# Backer_Boards_01April15.net
KiCad netlist of a schematic drawn in EAGLE
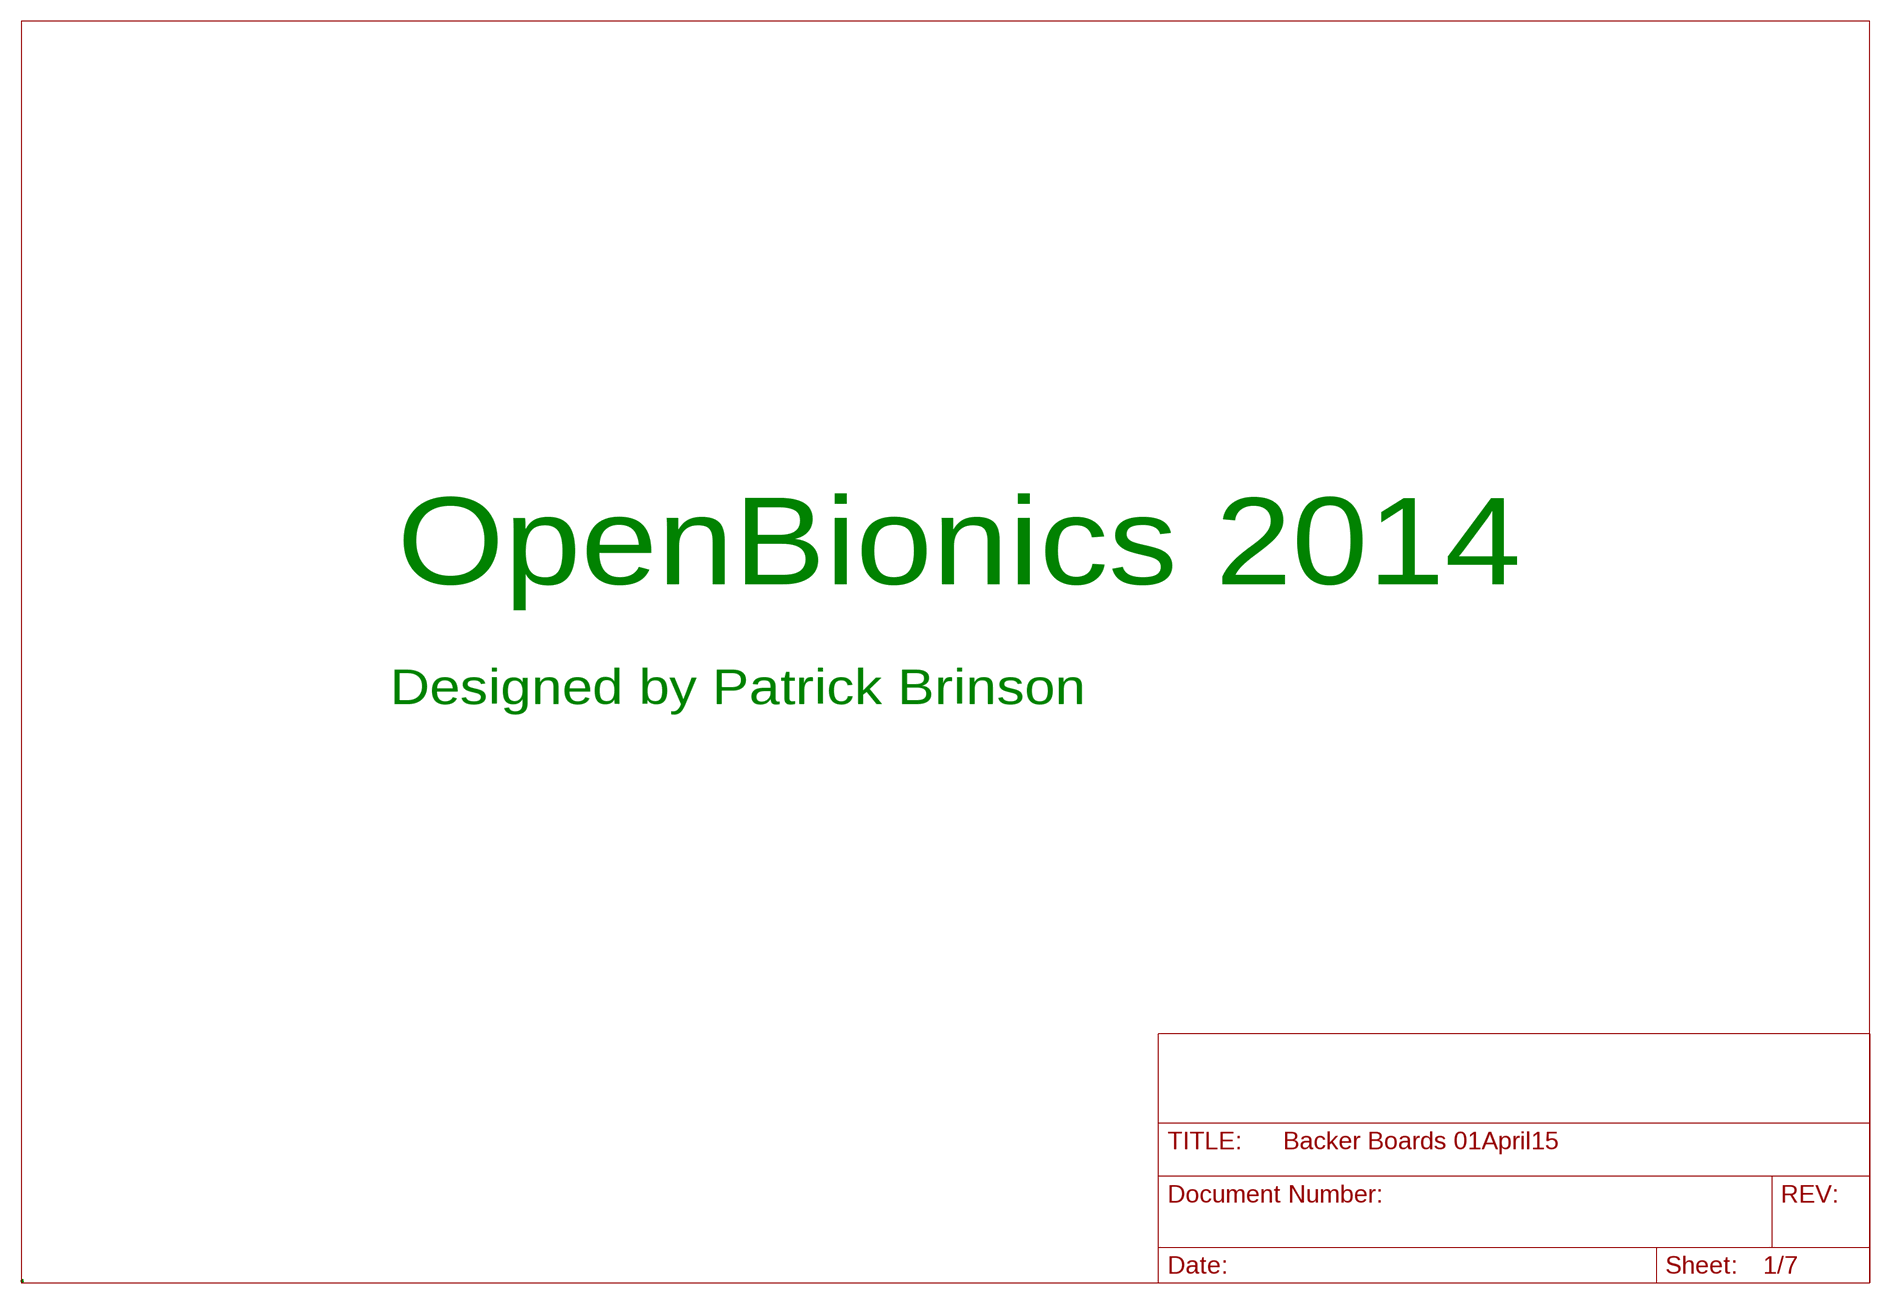
[diagram p0: schematic, sheet 1]
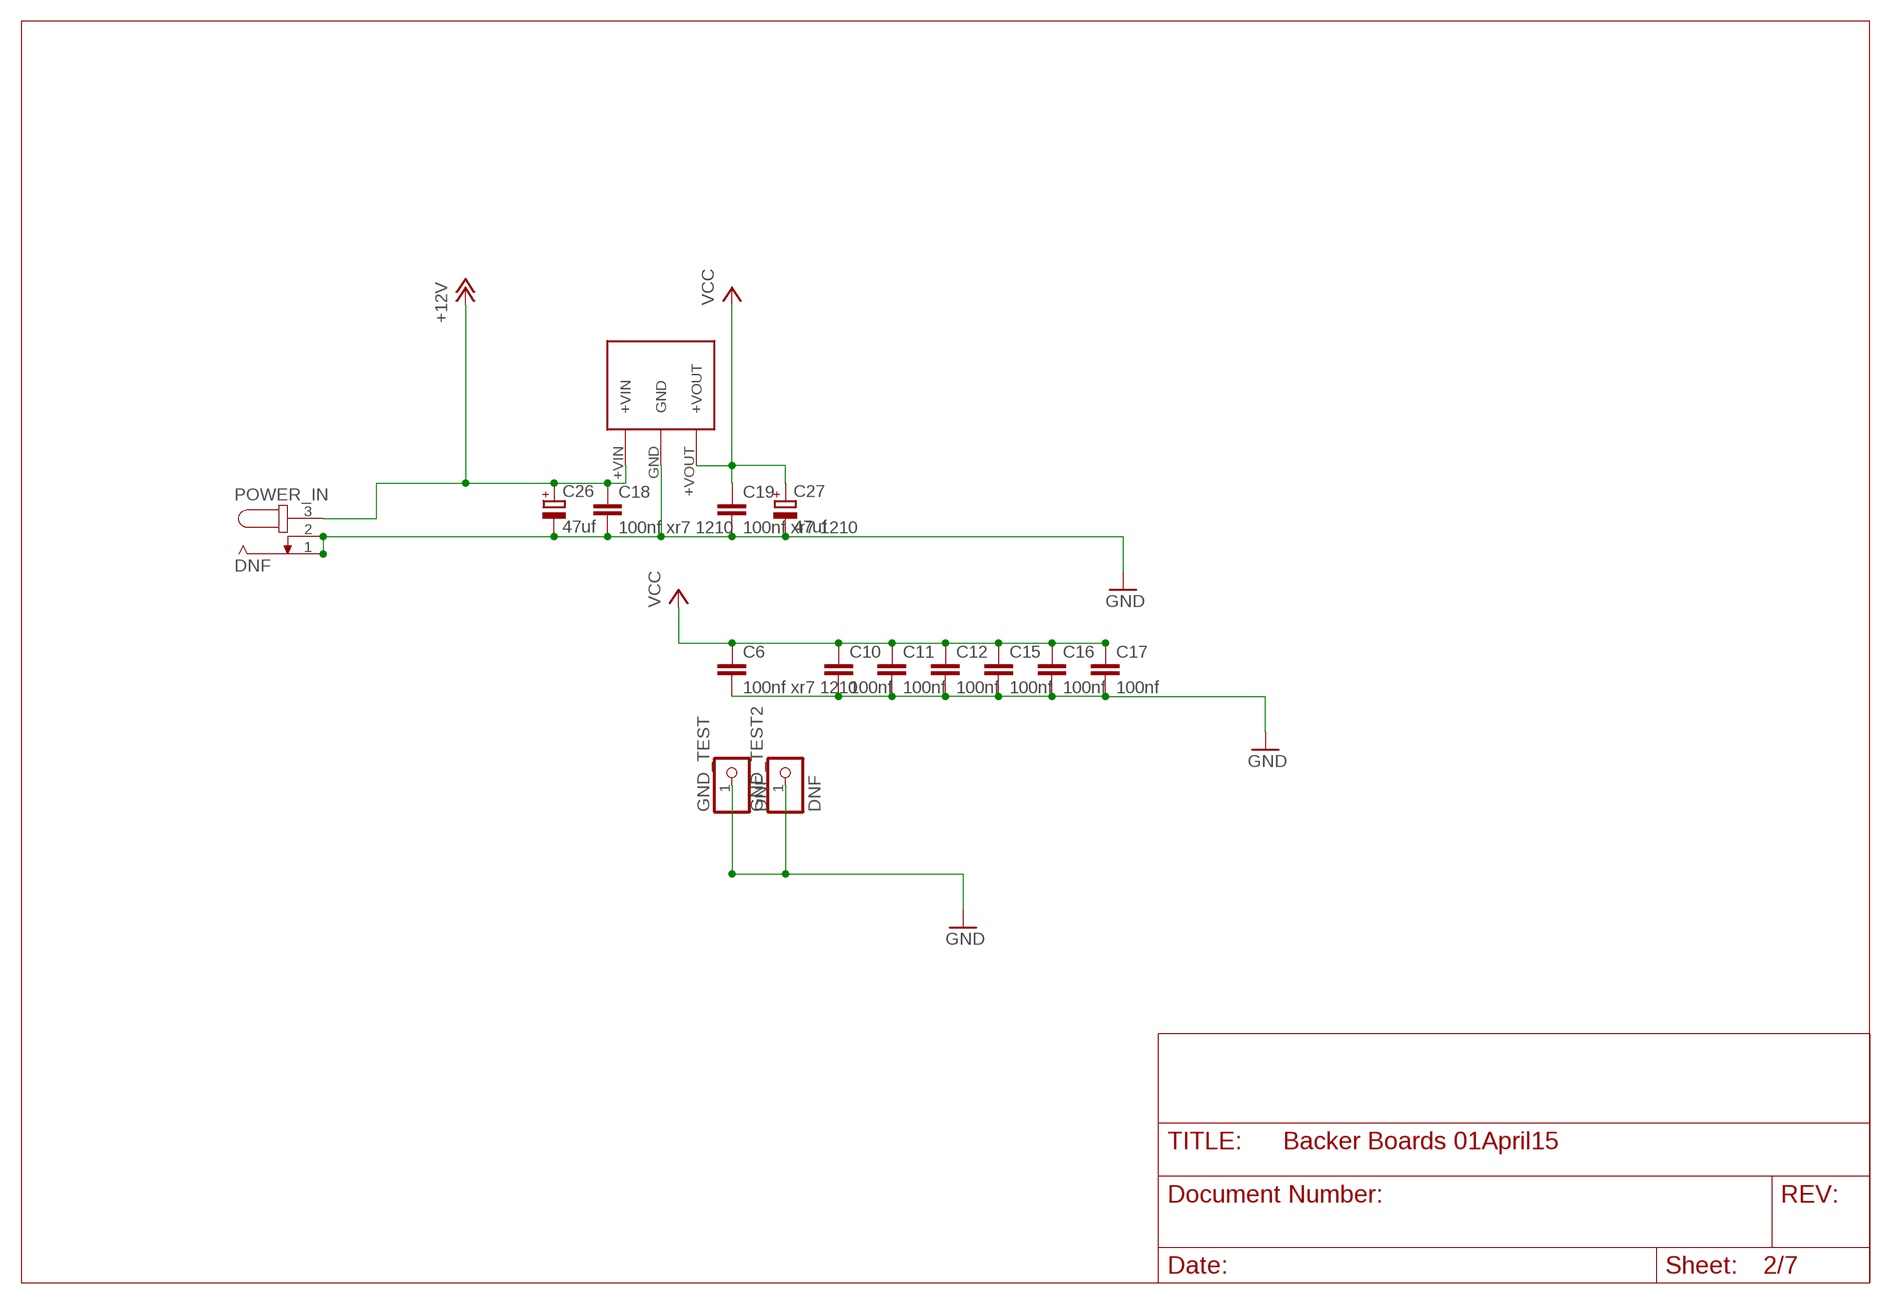
[diagram p1: schematic, sheet 2]
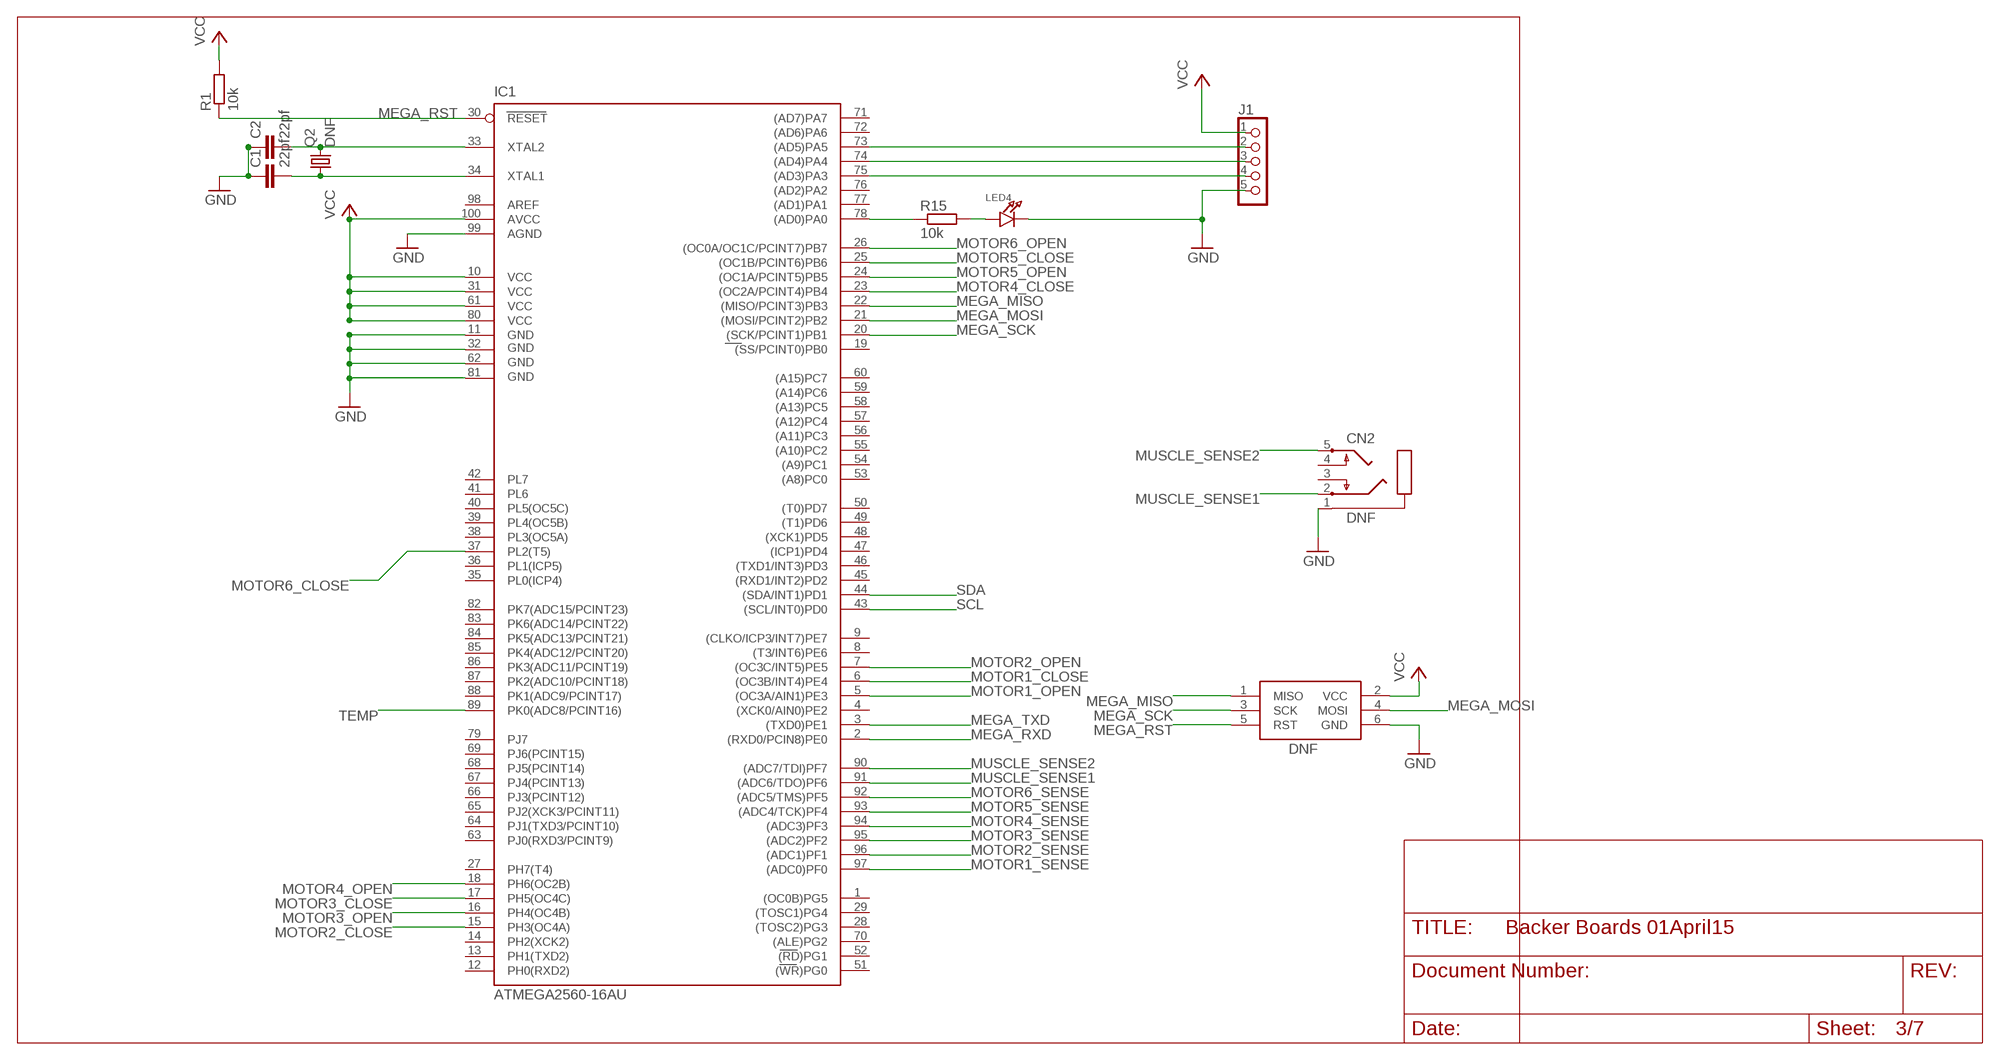
[diagram p2: schematic, sheet 3]
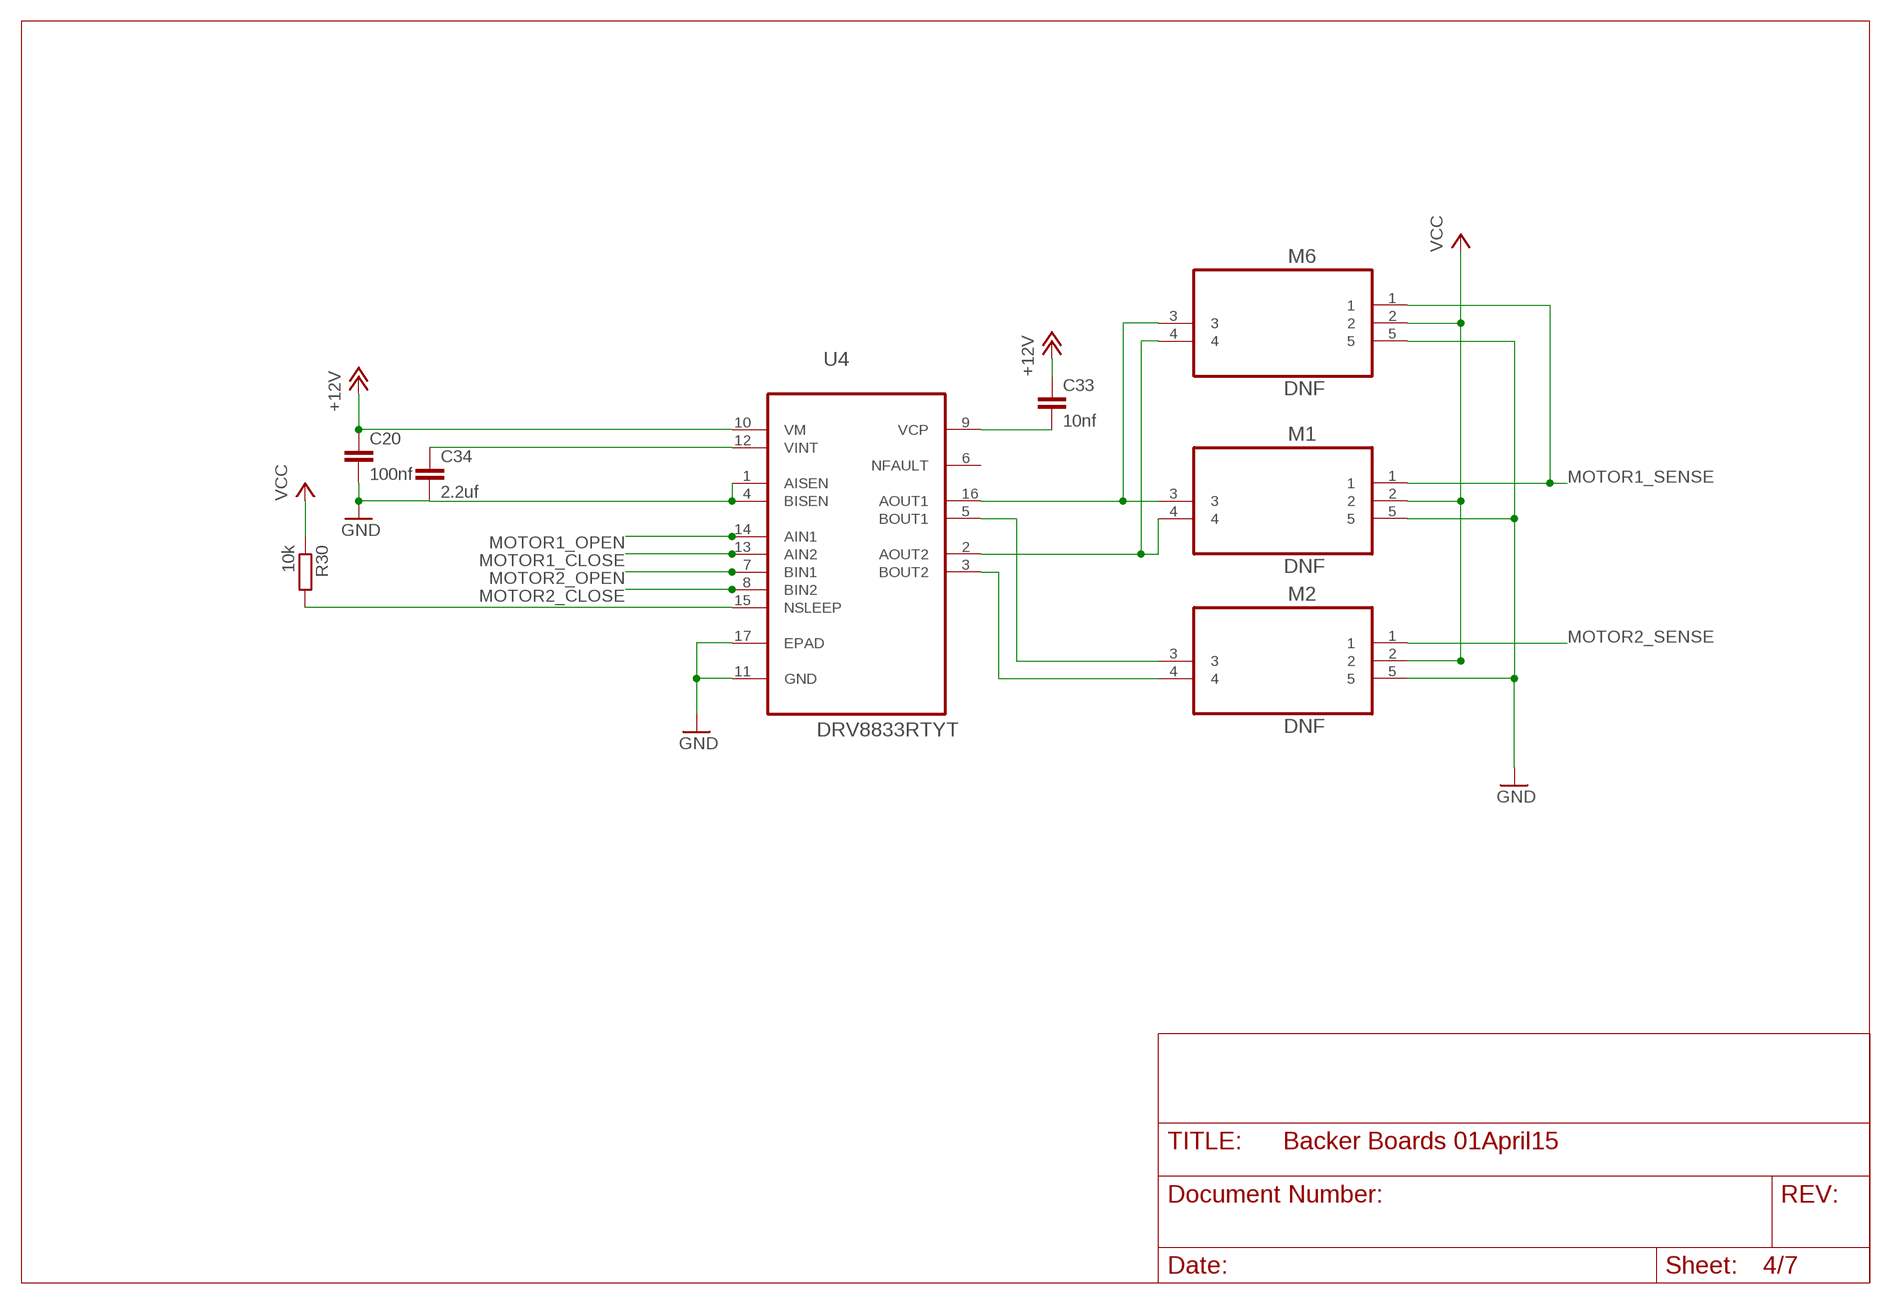
[diagram p3: schematic, sheet 4]
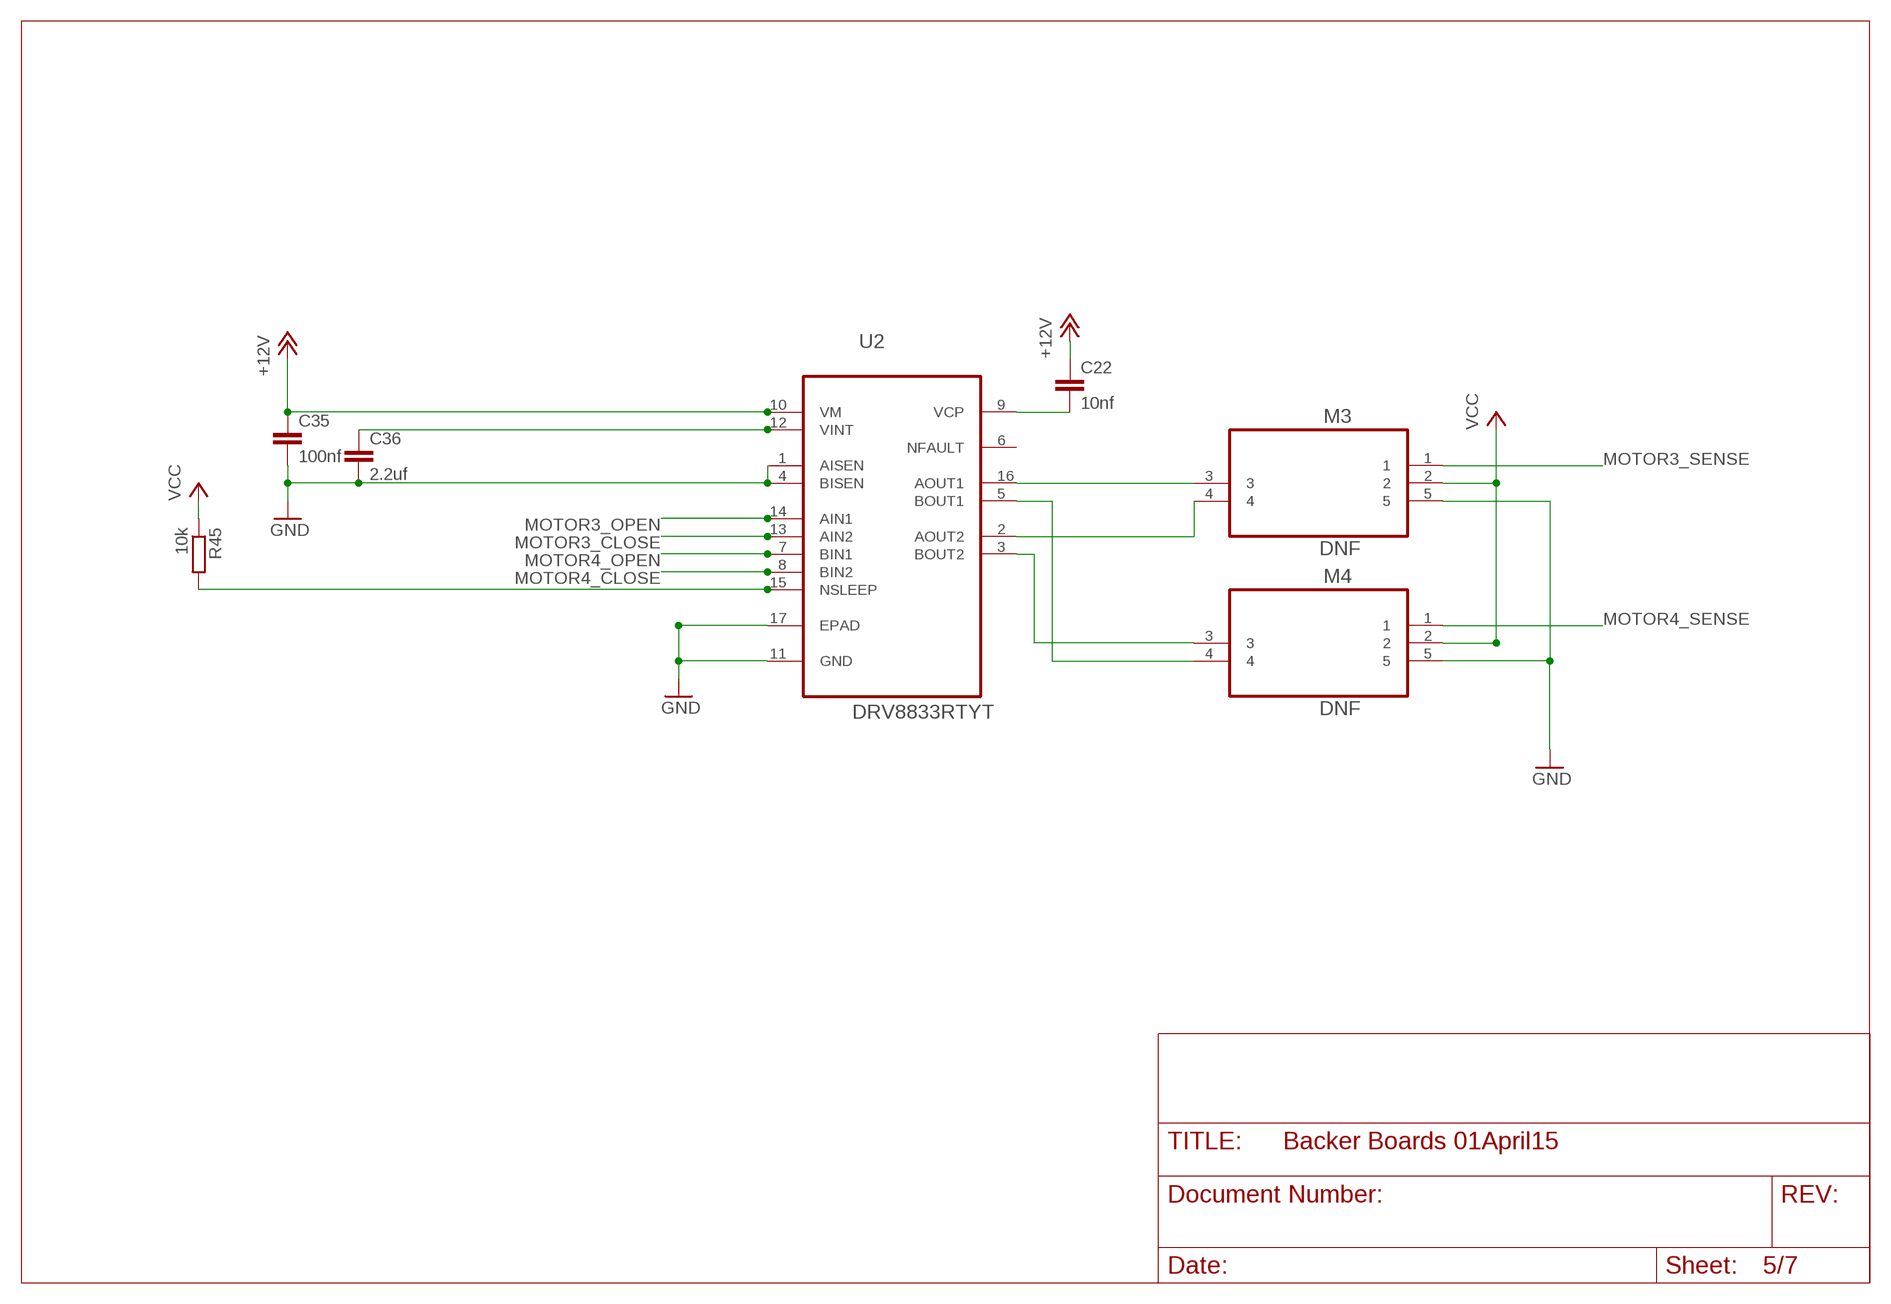
[diagram p4: schematic, sheet 5]
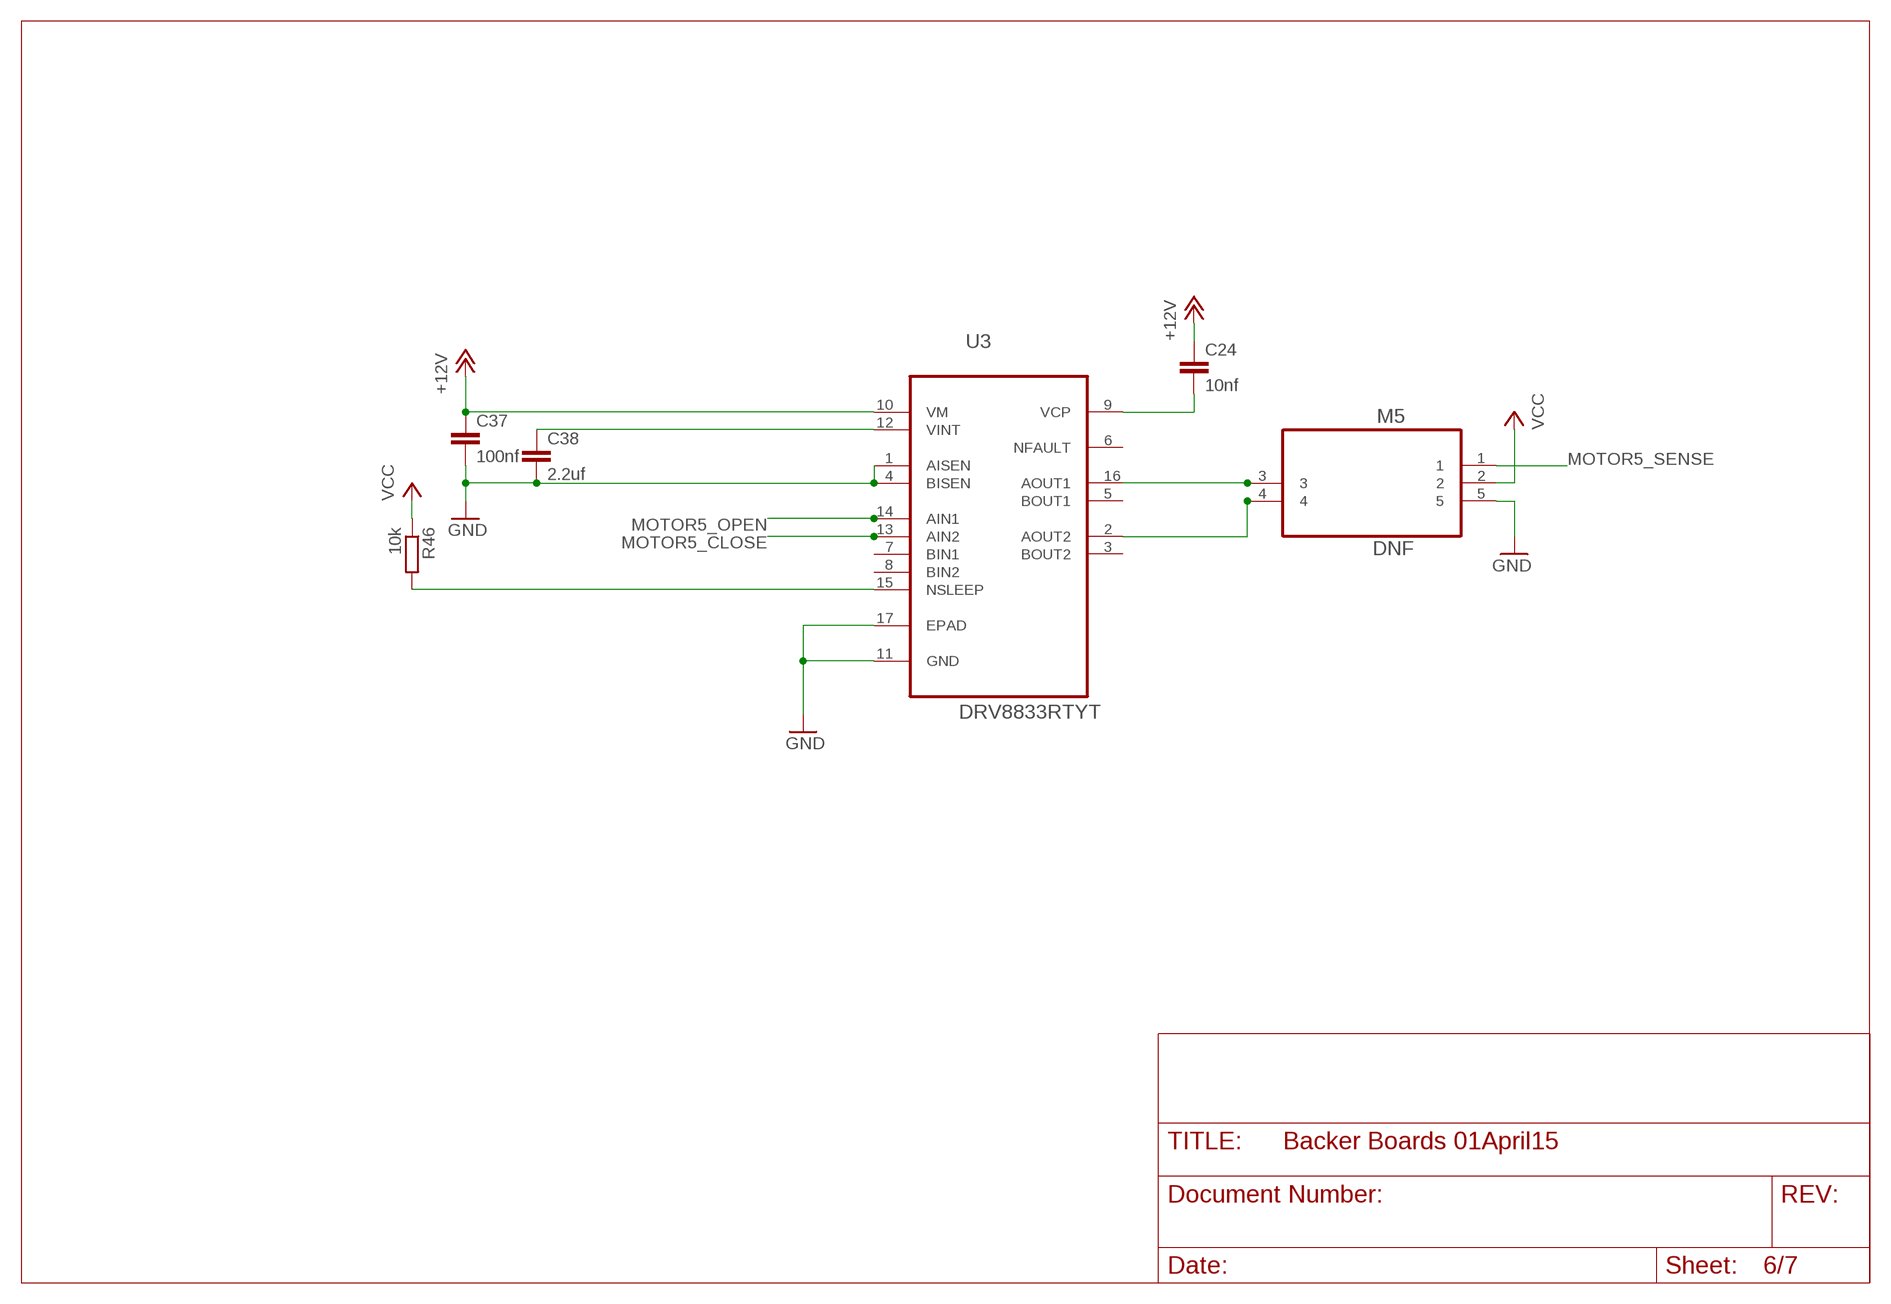
[diagram p5: schematic, sheet 6]
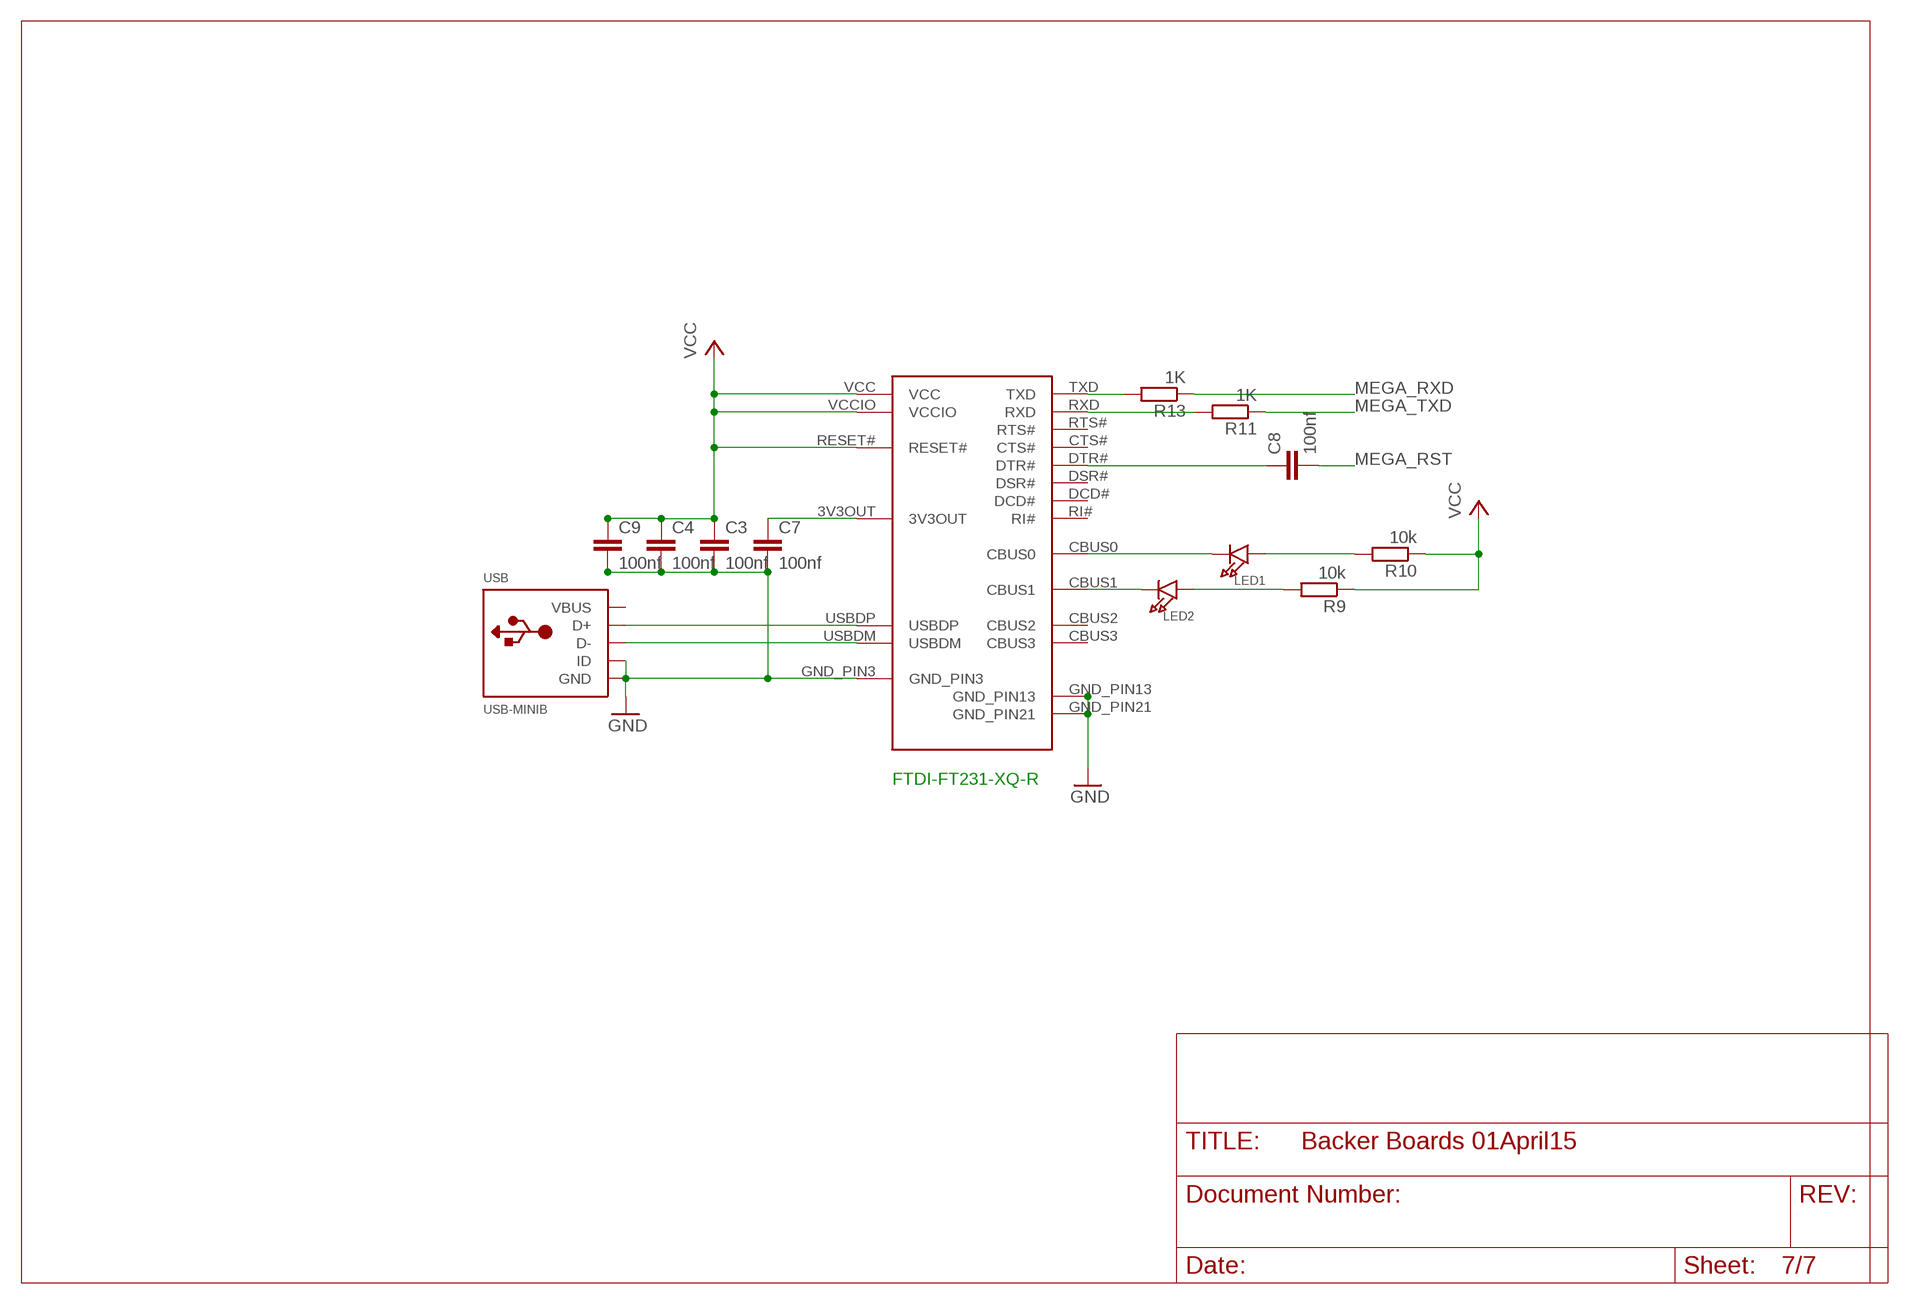
[diagram p6: schematic, sheet 7]

(export (version "E")
  (design (tool "Eeschema 10.0.6"))
  (components
    (comp (ref "C24")
      (value "10nf")
      (footprint "eagle-import:C0603")
      (libsource (lib "eagle-import") (part "C-EUC0603"))
    )
    (comp (ref "C37")
      (value "100nf")
      (footprint "eagle-import:C0603")
      (libsource (lib "eagle-import") (part "C-EUC0603"))
    )
    (comp (ref "C38")
      (value "2.2uf")
      (footprint "eagle-import:C0603")
      (libsource (lib "eagle-import") (part "C-EUC0603"))
    )
    (comp (ref "M5")
      (value "DNF")
      (footprint "eagle-import:FCI_SFW5R-1STE1LF")
      (fields (field (name "MPN") "SFW5R-1STE1LF"))
      (libsource (lib "eagle-import") (part "SFW5R-1STE1LF"))
    )
    (comp (ref "R46")
      (value "10k")
      (footprint "eagle-import:R0603")
      (libsource (lib "eagle-import") (part "R-EU_R0603"))
    )
    (comp (ref "U3")
      (value "DRV8833RTYT")
      (footprint "eagle-import:QFN65P400X400X80-17N")
      (fields (field (name "MPN") "DRV8833RTYT "))
      (libsource (lib "eagle-import") (part "DRV8833RTYT"))
    )
    (comp (ref "C1")
      (value "22pf")
      (footprint "eagle-import:C0603")
      (libsource (lib "eagle-import") (part "C-EUC0603"))
    )
    (comp (ref "C2")
      (value "22pf")
      (footprint "eagle-import:C0603")
      (libsource (lib "eagle-import") (part "C-EUC0603"))
    )
    (comp (ref "CN2")
      (value "DNF")
      (footprint "eagle-import:STX3100")
      (libsource (lib "eagle-import") (part "AUDIO_STEREOJACK"))
    )
    (comp (ref "DNF")
      (value "AVRISP-6")
      (footprint "eagle-import:AVRISP")
      (libsource (lib "eagle-import") (part "AVRISP-6"))
    )
    (comp (ref "IC1")
      (value "ATMEGA2560-16AU")
      (footprint "eagle-import:TQFP100")
      (libsource (lib "eagle-import") (part "ATMEGAAU2560-16"))
    )
    (comp (ref "J1")
      (value "DNF")
      (footprint "eagle-import:M1X5")
      (libsource (lib "eagle-import") (part "CON_HEADER_1X05-PTH"))
    )
    (comp (ref "LED4")
      (value "LED0805")
      (footprint "eagle-import:CHIPLED_0805")
      (libsource (lib "eagle-import") (part "LED0805"))
    )
    (comp (ref "Q2")
      (value "DNF")
      (footprint "eagle-import:HC49_S")
      (libsource (lib "eagle-import") (part "CRYSTALHC49S"))
    )
    (comp (ref "R1")
      (value "10k")
      (footprint "eagle-import:R0603")
      (libsource (lib "eagle-import") (part "R-EU_R0603"))
    )
    (comp (ref "R15")
      (value "10k")
      (footprint "eagle-import:R0603")
      (libsource (lib "eagle-import") (part "R-EU_R0603"))
    )
    (comp (ref "5V_REG")
      (value "DNF")
      (footprint "eagle-import:5V_RECOM_0.5A_REGULATOR")
      (libsource (lib "eagle-import") (part "5V_RECOM_0.5A_REGULATOR"))
    )
    (comp (ref "C6")
      (value "100nf xr7 1210")
      (footprint "eagle-import:C1210")
      (libsource (lib "eagle-import") (part "C-EUC1210"))
    )
    (comp (ref "C10")
      (value "100nf")
      (footprint "eagle-import:C0603")
      (libsource (lib "eagle-import") (part "C-EUC0603"))
    )
    (comp (ref "C11")
      (value "100nf")
      (footprint "eagle-import:C0603")
      (libsource (lib "eagle-import") (part "C-EUC0603"))
    )
    (comp (ref "C12")
      (value "100nf")
      (footprint "eagle-import:C0603")
      (libsource (lib "eagle-import") (part "C-EUC0603"))
    )
    (comp (ref "C15")
      (value "100nf")
      (footprint "eagle-import:C0603")
      (libsource (lib "eagle-import") (part "C-EUC0603"))
    )
    (comp (ref "C16")
      (value "100nf")
      (footprint "eagle-import:C0603")
      (libsource (lib "eagle-import") (part "C-EUC0603"))
    )
    (comp (ref "C17")
      (value "100nf")
      (footprint "eagle-import:C0603")
      (libsource (lib "eagle-import") (part "C-EUC0603"))
    )
    (comp (ref "C18")
      (value "100nf xr7 1210")
      (footprint "eagle-import:C1210")
      (libsource (lib "eagle-import") (part "C-EUC1210"))
    )
    (comp (ref "C19")
      (value "100nf xr7 1210")
      (footprint "eagle-import:C1210")
      (libsource (lib "eagle-import") (part "C-EUC1210"))
    )
    (comp (ref "C26")
      (value "47uf")
      (footprint "eagle-import:PANASONIC_C")
      (libsource (lib "eagle-import") (part "CPOL-EUC"))
    )
    (comp (ref "C27")
      (value "47uf")
      (footprint "eagle-import:PANASONIC_C")
      (libsource (lib "eagle-import") (part "CPOL-EUC"))
    )
    (comp (ref "GND_TEST")
      (value "DNF")
      (footprint "eagle-import:1X01_ROUND")
      (libsource (lib "eagle-import") (part "HEADER-1X1ROUND"))
    )
    (comp (ref "GND_TEST2")
      (value "DNF")
      (footprint "eagle-import:1X01_ROUND")
      (libsource (lib "eagle-import") (part "HEADER-1X1ROUND"))
    )
    (comp (ref "POWER_IN")
      (value "DNF")
      (footprint "eagle-import:SPC4078")
      (libsource (lib "eagle-import") (part "JACK-PLUG1"))
    )
    (comp (ref "C20")
      (value "100nf")
      (footprint "eagle-import:C0603")
      (libsource (lib "eagle-import") (part "C-EUC0603"))
    )
    (comp (ref "C33")
      (value "10nf")
      (footprint "eagle-import:C0603")
      (libsource (lib "eagle-import") (part "C-EUC0603"))
    )
    (comp (ref "C34")
      (value "2.2uf")
      (footprint "eagle-import:C0603")
      (libsource (lib "eagle-import") (part "C-EUC0603"))
    )
    (comp (ref "M1")
      (value "DNF")
      (footprint "eagle-import:FCI_SFW5R-1STE1LF")
      (fields (field (name "MPN") "SFW5R-1STE1LF"))
      (libsource (lib "eagle-import") (part "SFW5R-1STE1LF"))
    )
    (comp (ref "M2")
      (value "DNF")
      (footprint "eagle-import:FCI_SFW5R-1STE1LF")
      (fields (field (name "MPN") "SFW5R-1STE1LF"))
      (libsource (lib "eagle-import") (part "SFW5R-1STE1LF"))
    )
    (comp (ref "M6")
      (value "DNF")
      (footprint "eagle-import:FCI_SFW5R-1STE1LF")
      (fields (field (name "MPN") "SFW5R-1STE1LF"))
      (libsource (lib "eagle-import") (part "SFW5R-1STE1LF"))
    )
    (comp (ref "R30")
      (value "10k")
      (footprint "eagle-import:R0603")
      (libsource (lib "eagle-import") (part "R-EU_R0603"))
    )
    (comp (ref "U4")
      (value "DRV8833RTYT")
      (footprint "eagle-import:QFN65P400X400X80-17N")
      (fields (field (name "MPN") "DRV8833RTYT "))
      (libsource (lib "eagle-import") (part "DRV8833RTYT"))
    )
    (comp (ref "C3")
      (value "100nf")
      (footprint "eagle-import:C0603")
      (libsource (lib "eagle-import") (part "C-EUC0603"))
    )
    (comp (ref "C4")
      (value "100nf")
      (footprint "eagle-import:C0603")
      (libsource (lib "eagle-import") (part "C-EUC0603"))
    )
    (comp (ref "C7")
      (value "100nf")
      (footprint "eagle-import:C0603")
      (libsource (lib "eagle-import") (part "C-EUC0603"))
    )
    (comp (ref "C8")
      (value "100nf")
      (footprint "eagle-import:C0603")
      (libsource (lib "eagle-import") (part "C-EUC0603"))
    )
    (comp (ref "C9")
      (value "100nf")
      (footprint "eagle-import:C0603")
      (libsource (lib "eagle-import") (part "C-EUC0603"))
    )
    (comp (ref "FTDI-FT231-XQ-R")
      (value "FT231XQ-R")
      (footprint "eagle-import:FTDI_FT231XQ-R_PACKAGE")
      (libsource (lib "eagle-import") (part "FT231XQ-R"))
    )
    (comp (ref "LED1")
      (value "LED0805")
      (footprint "eagle-import:CHIPLED_0805")
      (libsource (lib "eagle-import") (part "LED0805"))
    )
    (comp (ref "LED2")
      (value "LED0805")
      (footprint "eagle-import:CHIPLED_0805")
      (libsource (lib "eagle-import") (part "LED0805"))
    )
    (comp (ref "R9")
      (value "10k")
      (footprint "eagle-import:R0603")
      (libsource (lib "eagle-import") (part "R-EU_R0603"))
    )
    (comp (ref "R10")
      (value "10k")
      (footprint "eagle-import:R0603")
      (libsource (lib "eagle-import") (part "R-EU_R0603"))
    )
    (comp (ref "R11")
      (value "1K")
      (footprint "eagle-import:R0603")
      (libsource (lib "eagle-import") (part "R-EU_R0603"))
    )
    (comp (ref "R13")
      (value "1K")
      (footprint "eagle-import:R0603")
      (libsource (lib "eagle-import") (part "R-EU_R0603"))
    )
    (comp (ref "USB")
      (value "USB-MINIB")
      (footprint "eagle-import:USB-MINIB")
      (libsource (lib "eagle-import") (part "USBMINIB"))
    )
    (comp (ref "C22")
      (value "10nf")
      (footprint "eagle-import:C0603")
      (libsource (lib "eagle-import") (part "C-EUC0603"))
    )
    (comp (ref "C35")
      (value "100nf")
      (footprint "eagle-import:C0603")
      (libsource (lib "eagle-import") (part "C-EUC0603"))
    )
    (comp (ref "C36")
      (value "2.2uf")
      (footprint "eagle-import:C0603")
      (libsource (lib "eagle-import") (part "C-EUC0603"))
    )
    (comp (ref "M3")
      (value "DNF")
      (footprint "eagle-import:FCI_SFW5R-1STE1LF")
      (fields (field (name "MPN") "SFW5R-1STE1LF"))
      (libsource (lib "eagle-import") (part "SFW5R-1STE1LF"))
    )
    (comp (ref "M4")
      (value "DNF")
      (footprint "eagle-import:FCI_SFW5R-1STE1LF")
      (fields (field (name "MPN") "SFW5R-1STE1LF"))
      (libsource (lib "eagle-import") (part "SFW5R-1STE1LF"))
    )
    (comp (ref "R45")
      (value "10k")
      (footprint "eagle-import:R0603")
      (libsource (lib "eagle-import") (part "R-EU_R0603"))
    )
    (comp (ref "U2")
      (value "DRV8833RTYT")
      (footprint "eagle-import:QFN65P400X400X80-17N")
      (fields (field (name "MPN") "DRV8833RTYT "))
      (libsource (lib "eagle-import") (part "DRV8833RTYT"))
    )
  )
  (nets
    (net (code "1") (name "+12V") (class "Default")
      (node (ref "5V_REG") (pin "+VIN") (pinfunction "+VIN_+VIN") (pintype "bidirectional"))
      (node (ref "C18") (pin "1") (pinfunction "1_1") (pintype "passive"))
      (node (ref "C20") (pin "1") (pinfunction "1_1") (pintype "passive"))
      (node (ref "C22") (pin "1") (pinfunction "1_1") (pintype "passive"))
      (node (ref "C24") (pin "1") (pinfunction "1_1") (pintype "passive"))
      (node (ref "C26") (pin "+") (pinfunction "+_+") (pintype "passive"))
      (node (ref "C33") (pin "1") (pinfunction "1_1") (pintype "passive"))
      (node (ref "C35") (pin "1") (pinfunction "1_1") (pintype "passive"))
      (node (ref "C37") (pin "1") (pinfunction "1_1") (pintype "passive"))
      (node (ref "POWER_IN") (pin "3") (pinfunction "3_3") (pintype "passive"))
      (node (ref "U2") (pin "10") (pinfunction "VM_10") (pintype "power_in"))
      (node (ref "U3") (pin "10") (pinfunction "VM_10") (pintype "power_in"))
      (node (ref "U4") (pin "10") (pinfunction "VM_10") (pintype "power_in"))
    )
    (net (code "2") (name "GND") (class "Default")
      (node (ref "5V_REG") (pin "GND") (pinfunction "GND_GND") (pintype "bidirectional"))
      (node (ref "C1") (pin "1") (pinfunction "1_1") (pintype "passive"))
      (node (ref "C10") (pin "2") (pinfunction "2_2") (pintype "passive"))
      (node (ref "C11") (pin "2") (pinfunction "2_2") (pintype "passive"))
      (node (ref "C12") (pin "2") (pinfunction "2_2") (pintype "passive"))
      (node (ref "C15") (pin "2") (pinfunction "2_2") (pintype "passive"))
      (node (ref "C16") (pin "2") (pinfunction "2_2") (pintype "passive"))
      (node (ref "C17") (pin "2") (pinfunction "2_2") (pintype "passive"))
      (node (ref "C18") (pin "2") (pinfunction "2_2") (pintype "passive"))
      (node (ref "C19") (pin "2") (pinfunction "2_2") (pintype "passive"))
      (node (ref "C2") (pin "1") (pinfunction "1_1") (pintype "passive"))
      (node (ref "C20") (pin "2") (pinfunction "2_2") (pintype "passive"))
      (node (ref "C26") (pin "-") (pinfunction "-_-") (pintype "passive"))
      (node (ref "C27") (pin "-") (pinfunction "-_-") (pintype "passive"))
      (node (ref "C3") (pin "2") (pinfunction "2_2") (pintype "passive"))
      (node (ref "C34") (pin "2") (pinfunction "2_2") (pintype "passive"))
      (node (ref "C35") (pin "2") (pinfunction "2_2") (pintype "passive"))
      (node (ref "C36") (pin "2") (pinfunction "2_2") (pintype "passive"))
      (node (ref "C37") (pin "2") (pinfunction "2_2") (pintype "passive"))
      (node (ref "C38") (pin "2") (pinfunction "2_2") (pintype "passive"))
      (node (ref "C4") (pin "2") (pinfunction "2_2") (pintype "passive"))
      (node (ref "C6") (pin "2") (pinfunction "2_2") (pintype "passive"))
      (node (ref "C7") (pin "2") (pinfunction "2_2") (pintype "passive"))
      (node (ref "C9") (pin "2") (pinfunction "2_2") (pintype "passive"))
      (node (ref "CN2") (pin "1") (pinfunction "1_1") (pintype "passive"))
      (node (ref "DNF") (pin "6") (pinfunction "GND_6") (pintype "power_in"))
      (node (ref "FTDI-FT231-XQ-R") (pin "GND_PIN13") (pinfunction "GND_PIN13_GND_PIN13") (pintype "bidirectional"))
      (node (ref "FTDI-FT231-XQ-R") (pin "GND_PIN21") (pinfunction "GND_PIN21_GND_PIN21") (pintype "bidirectional"))
      (node (ref "FTDI-FT231-XQ-R") (pin "GND_PIN3") (pinfunction "GND_PIN3_GND_PIN3") (pintype "bidirectional"))
      (node (ref "GND_TEST") (pin "1") (pinfunction "1_1") (pintype "passive"))
      (node (ref "GND_TEST2") (pin "1") (pinfunction "1_1") (pintype "passive"))
      (node (ref "IC1") (pin "11") (pinfunction "GND_11") (pintype "power_in"))
      (node (ref "IC1") (pin "32") (pinfunction "GND1_32") (pintype "power_in"))
      (node (ref "IC1") (pin "62") (pinfunction "GND2_62") (pintype "power_in"))
      (node (ref "IC1") (pin "81") (pinfunction "GND3_81") (pintype "power_in"))
      (node (ref "IC1") (pin "99") (pinfunction "AGND_99") (pintype "power_in"))
      (node (ref "J1") (pin "5") (pinfunction "5_5") (pintype "bidirectional"))
      (node (ref "LED4") (pin "C") (pinfunction "C_C") (pintype "passive"))
      (node (ref "M1") (pin "5") (pinfunction "5_5") (pintype "passive"))
      (node (ref "M2") (pin "5") (pinfunction "5_5") (pintype "passive"))
      (node (ref "M3") (pin "5") (pinfunction "5_5") (pintype "passive"))
      (node (ref "M4") (pin "5") (pinfunction "5_5") (pintype "passive"))
      (node (ref "M5") (pin "5") (pinfunction "5_5") (pintype "passive"))
      (node (ref "M6") (pin "5") (pinfunction "5_5") (pintype "passive"))
      (node (ref "POWER_IN") (pin "1") (pinfunction "1_1") (pintype "passive"))
      (node (ref "POWER_IN") (pin "2") (pinfunction "2_2") (pintype "passive"))
      (node (ref "U2") (pin "1") (pinfunction "AISEN_1") (pintype "bidirectional"))
      (node (ref "U2") (pin "11") (pinfunction "GND_11") (pintype "passive"))
      (node (ref "U2") (pin "17") (pinfunction "EPAD_17") (pintype "passive"))
      (node (ref "U2") (pin "4") (pinfunction "BISEN_4") (pintype "bidirectional"))
      (node (ref "U3") (pin "1") (pinfunction "AISEN_1") (pintype "bidirectional"))
      (node (ref "U3") (pin "11") (pinfunction "GND_11") (pintype "passive"))
      (node (ref "U3") (pin "17") (pinfunction "EPAD_17") (pintype "passive"))
      (node (ref "U3") (pin "4") (pinfunction "BISEN_4") (pintype "bidirectional"))
      (node (ref "U4") (pin "1") (pinfunction "AISEN_1") (pintype "bidirectional"))
      (node (ref "U4") (pin "11") (pinfunction "GND_11") (pintype "passive"))
      (node (ref "U4") (pin "17") (pinfunction "EPAD_17") (pintype "passive"))
      (node (ref "U4") (pin "4") (pinfunction "BISEN_4") (pintype "bidirectional"))
      (node (ref "USB") (pin "GND") (pinfunction "GND_GND") (pintype "power_in"))
      (node (ref "USB") (pin "ID") (pinfunction "ID_ID") (pintype "bidirectional"))
    )
    (net (code "3") (name "MEGA_MISO") (class "Default")
      (node (ref "DNF") (pin "1") (pinfunction "MISO_1") (pintype "input"))
      (node (ref "IC1") (pin "22") (pinfunction "(MISO/PCINT3)PB3_22") (pintype "bidirectional"))
    )
    (net (code "4") (name "MEGA_MOSI") (class "Default")
      (node (ref "DNF") (pin "4") (pinfunction "MOSI_4") (pintype "output"))
      (node (ref "IC1") (pin "21") (pinfunction "(MOSI/PCINT2)PB2_21") (pintype "bidirectional"))
    )
    (net (code "5") (name "MEGA_RST") (class "Default")
      (node (ref "C8") (pin "2") (pinfunction "2_2") (pintype "passive"))
      (node (ref "DNF") (pin "5") (pinfunction "RST_5") (pintype "output"))
      (node (ref "IC1") (pin "30") (pinfunction "RESET_30") (pintype "input"))
      (node (ref "R1") (pin "1") (pinfunction "1_1") (pintype "passive"))
    )
    (net (code "6") (name "MEGA_RXD") (class "Default")
      (node (ref "IC1") (pin "2") (pinfunction "(RXD0/PCIN8)PE0_2") (pintype "bidirectional"))
      (node (ref "R13") (pin "1") (pinfunction "1_1") (pintype "passive"))
    )
    (net (code "7") (name "MEGA_SCK") (class "Default")
      (node (ref "DNF") (pin "3") (pinfunction "SCK_3") (pintype "output"))
      (node (ref "IC1") (pin "20") (pinfunction "(SCK/PCINT1)PB1_20") (pintype "bidirectional"))
    )
    (net (code "8") (name "MEGA_TXD") (class "Default")
      (node (ref "IC1") (pin "3") (pinfunction "(TXD0)PE1_3") (pintype "bidirectional"))
      (node (ref "R11") (pin "1") (pinfunction "1_1") (pintype "passive"))
    )
    (net (code "9") (name "MOTOR1_CLOSE") (class "Default")
      (node (ref "IC1") (pin "6") (pinfunction "(OC3B/INT4)PE4_6") (pintype "bidirectional"))
      (node (ref "U4") (pin "13") (pinfunction "AIN2_13") (pintype "input"))
    )
    (net (code "10") (name "MOTOR1_OPEN") (class "Default")
      (node (ref "IC1") (pin "5") (pinfunction "(OC3A/AIN1)PE3_5") (pintype "bidirectional"))
      (node (ref "U4") (pin "14") (pinfunction "AIN1_14") (pintype "input"))
    )
    (net (code "11") (name "MOTOR1_SENSE") (class "Default")
      (node (ref "IC1") (pin "97") (pinfunction "(ADC0)PF0_97") (pintype "bidirectional"))
      (node (ref "M1") (pin "1") (pinfunction "1_1") (pintype "passive"))
      (node (ref "M6") (pin "1") (pinfunction "1_1") (pintype "passive"))
    )
    (net (code "12") (name "MOTOR2_CLOSE") (class "Default")
      (node (ref "IC1") (pin "15") (pinfunction "PH3(OC4A)_15") (pintype "bidirectional"))
      (node (ref "U4") (pin "8") (pinfunction "BIN2_8") (pintype "input"))
    )
    (net (code "13") (name "MOTOR2_OPEN") (class "Default")
      (node (ref "IC1") (pin "7") (pinfunction "(OC3C/INT5)PE5_7") (pintype "bidirectional"))
      (node (ref "U4") (pin "7") (pinfunction "BIN1_7") (pintype "input"))
    )
    (net (code "14") (name "MOTOR2_SENSE") (class "Default")
      (node (ref "IC1") (pin "96") (pinfunction "(ADC1)PF1_96") (pintype "bidirectional"))
      (node (ref "M2") (pin "1") (pinfunction "1_1") (pintype "passive"))
    )
    (net (code "15") (name "MOTOR3_CLOSE") (class "Default")
      (node (ref "IC1") (pin "17") (pinfunction "PH5(OC4C)_17") (pintype "bidirectional"))
      (node (ref "U2") (pin "13") (pinfunction "AIN2_13") (pintype "input"))
    )
    (net (code "16") (name "MOTOR3_OPEN") (class "Default")
      (node (ref "IC1") (pin "16") (pinfunction "PH4(OC4B)_16") (pintype "bidirectional"))
      (node (ref "U2") (pin "14") (pinfunction "AIN1_14") (pintype "input"))
    )
    (net (code "17") (name "MOTOR3_SENSE") (class "Default")
      (node (ref "IC1") (pin "95") (pinfunction "(ADC2)PF2_95") (pintype "bidirectional"))
      (node (ref "M3") (pin "1") (pinfunction "1_1") (pintype "passive"))
    )
    (net (code "18") (name "MOTOR4_CLOSE") (class "Default")
      (node (ref "IC1") (pin "23") (pinfunction "(OC2A/PCINT4)PB4_23") (pintype "bidirectional"))
      (node (ref "U2") (pin "8") (pinfunction "BIN2_8") (pintype "input"))
    )
    (net (code "19") (name "MOTOR4_OPEN") (class "Default")
      (node (ref "IC1") (pin "18") (pinfunction "PH6(OC2B)_18") (pintype "bidirectional"))
      (node (ref "U2") (pin "7") (pinfunction "BIN1_7") (pintype "input"))
    )
    (net (code "20") (name "MOTOR4_SENSE") (class "Default")
      (node (ref "IC1") (pin "94") (pinfunction "(ADC3)PF3_94") (pintype "bidirectional"))
      (node (ref "M4") (pin "1") (pinfunction "1_1") (pintype "passive"))
    )
    (net (code "21") (name "MOTOR5_CLOSE") (class "Default")
      (node (ref "IC1") (pin "25") (pinfunction "(OC1B/PCINT6)PB6_25") (pintype "bidirectional"))
      (node (ref "U3") (pin "13") (pinfunction "AIN2_13") (pintype "input"))
    )
    (net (code "22") (name "MOTOR5_OPEN") (class "Default")
      (node (ref "IC1") (pin "24") (pinfunction "(OC1A/PCINT5)PB5_24") (pintype "bidirectional"))
      (node (ref "U3") (pin "14") (pinfunction "AIN1_14") (pintype "input"))
    )
    (net (code "23") (name "MOTOR5_SENSE") (class "Default")
      (node (ref "IC1") (pin "93") (pinfunction "(ADC4/TCK)PF4_93") (pintype "bidirectional"))
      (node (ref "M5") (pin "1") (pinfunction "1_1") (pintype "passive"))
    )
    (net (code "24") (name "MOTOR6_CLOSE") (class "Default")
      (node (ref "IC1") (pin "37") (pinfunction "PL2(T5)_37") (pintype "bidirectional"))
    )
    (net (code "25") (name "MOTOR6_OPEN") (class "Default")
      (node (ref "IC1") (pin "26") (pinfunction "(OC0A/OC1C/PCINT7)PB7_26") (pintype "bidirectional"))
    )
    (net (code "26") (name "MOTOR6_SENSE") (class "Default")
      (node (ref "IC1") (pin "92") (pinfunction "(ADC5/TMS)PF5_92") (pintype "bidirectional"))
    )
    (net (code "27") (name "MUSCLE_SENSE1") (class "Default")
      (node (ref "CN2") (pin "2") (pinfunction "2_2") (pintype "passive"))
      (node (ref "IC1") (pin "91") (pinfunction "(ADC6/TDO)PF6_91") (pintype "bidirectional"))
    )
    (net (code "28") (name "MUSCLE_SENSE2") (class "Default")
      (node (ref "CN2") (pin "5") (pinfunction "5_5") (pintype "passive"))
      (node (ref "IC1") (pin "90") (pinfunction "(ADC7/TDI)PF7_90") (pintype "bidirectional"))
    )
    (net (code "29") (name "Net-(C7-Pad1)") (class "Default")
      (node (ref "C7") (pin "1") (pinfunction "1_1") (pintype "passive"))
      (node (ref "FTDI-FT231-XQ-R") (pin "3V3OUT") (pinfunction "3V3OUT_3V3OUT") (pintype "bidirectional"))
    )
    (net (code "30") (name "Net-(C8-Pad1)") (class "Default")
      (node (ref "C8") (pin "1") (pinfunction "1_1") (pintype "passive"))
      (node (ref "FTDI-FT231-XQ-R") (pin "DTR#") (pinfunction "DTR#_DTR#") (pintype "bidirectional"))
    )
    (net (code "31") (name "Net-(FTDI-FT231-XQ-R-PadCBUS0)") (class "Default")
      (node (ref "FTDI-FT231-XQ-R") (pin "CBUS0") (pinfunction "CBUS0_CBUS0") (pintype "bidirectional"))
      (node (ref "LED1") (pin "C") (pinfunction "C_C") (pintype "passive"))
    )
    (net (code "32") (name "Net-(FTDI-FT231-XQ-R-PadCBUS1)") (class "Default")
      (node (ref "FTDI-FT231-XQ-R") (pin "CBUS1") (pinfunction "CBUS1_CBUS1") (pintype "bidirectional"))
      (node (ref "LED2") (pin "C") (pinfunction "C_C") (pintype "passive"))
    )
    (net (code "33") (name "Net-(FTDI-FT231-XQ-R-PadRXD)") (class "Default")
      (node (ref "FTDI-FT231-XQ-R") (pin "RXD") (pinfunction "RXD_RXD") (pintype "bidirectional"))
      (node (ref "R11") (pin "2") (pinfunction "2_2") (pintype "passive"))
    )
    (net (code "34") (name "Net-(FTDI-FT231-XQ-R-PadTXD)") (class "Default")
      (node (ref "FTDI-FT231-XQ-R") (pin "TXD") (pinfunction "TXD_TXD") (pintype "bidirectional"))
      (node (ref "R13") (pin "2") (pinfunction "2_2") (pintype "passive"))
    )
    (net (code "35") (name "Net-(FTDI-FT231-XQ-R-PadUSBDM)") (class "Default")
      (node (ref "FTDI-FT231-XQ-R") (pin "USBDM") (pinfunction "USBDM_USBDM") (pintype "bidirectional"))
      (node (ref "USB") (pin "D-") (pinfunction "D-_D-") (pintype "bidirectional"))
    )
    (net (code "36") (name "Net-(FTDI-FT231-XQ-R-PadUSBDP)") (class "Default")
      (node (ref "FTDI-FT231-XQ-R") (pin "USBDP") (pinfunction "USBDP_USBDP") (pintype "bidirectional"))
      (node (ref "USB") (pin "D+") (pinfunction "D+_D+") (pintype "bidirectional"))
    )
    (net (code "37") (name "Net-(IC1-(AD0)PA0)") (class "Default")
      (node (ref "IC1") (pin "78") (pinfunction "(AD0)PA0_78") (pintype "bidirectional"))
      (node (ref "R15") (pin "1") (pinfunction "1_1") (pintype "passive"))
    )
    (net (code "38") (name "Net-(IC1-(AD3)PA3)") (class "Default")
      (node (ref "IC1") (pin "75") (pinfunction "(AD3)PA3_75") (pintype "bidirectional"))
      (node (ref "J1") (pin "4") (pinfunction "4_4") (pintype "bidirectional"))
    )
    (net (code "39") (name "Net-(IC1-(AD4)PA4)") (class "Default")
      (node (ref "IC1") (pin "74") (pinfunction "(AD4)PA4_74") (pintype "bidirectional"))
      (node (ref "J1") (pin "3") (pinfunction "3_3") (pintype "bidirectional"))
    )
    (net (code "40") (name "Net-(IC1-(AD5)PA5)") (class "Default")
      (node (ref "IC1") (pin "73") (pinfunction "(AD5)PA5_73") (pintype "bidirectional"))
      (node (ref "J1") (pin "2") (pinfunction "2_2") (pintype "bidirectional"))
    )
    (net (code "41") (name "Net-(IC1-XTAL1)") (class "Default")
      (node (ref "C1") (pin "2") (pinfunction "2_2") (pintype "passive"))
      (node (ref "IC1") (pin "34") (pinfunction "XTAL1_34") (pintype "input"))
      (node (ref "Q2") (pin "1") (pinfunction "1_1") (pintype "passive"))
    )
    (net (code "42") (name "Net-(IC1-XTAL2)") (class "Default")
      (node (ref "C2") (pin "2") (pinfunction "2_2") (pintype "passive"))
      (node (ref "IC1") (pin "33") (pinfunction "XTAL2_33") (pintype "output"))
      (node (ref "Q2") (pin "2") (pinfunction "2_2") (pintype "passive"))
    )
    (net (code "43") (name "Net-(LED1-PadA)") (class "Default")
      (node (ref "LED1") (pin "A") (pinfunction "A_A") (pintype "passive"))
      (node (ref "R10") (pin "2") (pinfunction "2_2") (pintype "passive"))
    )
    (net (code "44") (name "Net-(LED2-PadA)") (class "Default")
      (node (ref "LED2") (pin "A") (pinfunction "A_A") (pintype "passive"))
      (node (ref "R9") (pin "2") (pinfunction "2_2") (pintype "passive"))
    )
    (net (code "45") (name "Net-(LED4-PadA)") (class "Default")
      (node (ref "LED4") (pin "A") (pinfunction "A_A") (pintype "passive"))
      (node (ref "R15") (pin "2") (pinfunction "2_2") (pintype "passive"))
    )
    (net (code "46") (name "Net-(U2-AOUT1)") (class "Default")
      (node (ref "M3") (pin "3") (pinfunction "3_3") (pintype "passive"))
      (node (ref "U2") (pin "16") (pinfunction "AOUT1_16") (pintype "output"))
    )
    (net (code "47") (name "Net-(U2-AOUT2)") (class "Default")
      (node (ref "M3") (pin "4") (pinfunction "4_4") (pintype "passive"))
      (node (ref "U2") (pin "2") (pinfunction "AOUT2_2") (pintype "output"))
    )
    (net (code "48") (name "Net-(U2-BOUT1)") (class "Default")
      (node (ref "M4") (pin "4") (pinfunction "4_4") (pintype "passive"))
      (node (ref "U2") (pin "5") (pinfunction "BOUT1_5") (pintype "bidirectional"))
    )
    (net (code "49") (name "Net-(U2-BOUT2)") (class "Default")
      (node (ref "M4") (pin "3") (pinfunction "3_3") (pintype "passive"))
      (node (ref "U2") (pin "3") (pinfunction "BOUT2_3") (pintype "output"))
    )
    (net (code "50") (name "Net-(U2-NSLEEP)") (class "Default")
      (node (ref "R45") (pin "2") (pinfunction "2_2") (pintype "passive"))
      (node (ref "U2") (pin "15") (pinfunction "NSLEEP_15") (pintype "input"))
    )
    (net (code "51") (name "Net-(U2-VCP)") (class "Default")
      (node (ref "C22") (pin "2") (pinfunction "2_2") (pintype "passive"))
      (node (ref "U2") (pin "9") (pinfunction "VCP_9") (pintype "bidirectional"))
    )
    (net (code "52") (name "Net-(U2-VINT)") (class "Default")
      (node (ref "C36") (pin "1") (pinfunction "1_1") (pintype "passive"))
      (node (ref "U2") (pin "12") (pinfunction "VINT_12") (pintype "power_in"))
    )
    (net (code "53") (name "Net-(U3-AOUT1)") (class "Default")
      (node (ref "M5") (pin "3") (pinfunction "3_3") (pintype "passive"))
      (node (ref "U3") (pin "16") (pinfunction "AOUT1_16") (pintype "output"))
    )
    (net (code "54") (name "Net-(U3-AOUT2)") (class "Default")
      (node (ref "M5") (pin "4") (pinfunction "4_4") (pintype "passive"))
      (node (ref "U3") (pin "2") (pinfunction "AOUT2_2") (pintype "output"))
    )
    (net (code "55") (name "Net-(U3-NSLEEP)") (class "Default")
      (node (ref "R46") (pin "2") (pinfunction "2_2") (pintype "passive"))
      (node (ref "U3") (pin "15") (pinfunction "NSLEEP_15") (pintype "input"))
    )
    (net (code "56") (name "Net-(U3-VCP)") (class "Default")
      (node (ref "C24") (pin "2") (pinfunction "2_2") (pintype "passive"))
      (node (ref "U3") (pin "9") (pinfunction "VCP_9") (pintype "bidirectional"))
    )
    (net (code "57") (name "Net-(U3-VINT)") (class "Default")
      (node (ref "C38") (pin "1") (pinfunction "1_1") (pintype "passive"))
      (node (ref "U3") (pin "12") (pinfunction "VINT_12") (pintype "power_in"))
    )
    (net (code "58") (name "Net-(U4-AOUT1)") (class "Default")
      (node (ref "M1") (pin "3") (pinfunction "3_3") (pintype "passive"))
      (node (ref "M6") (pin "3") (pinfunction "3_3") (pintype "passive"))
      (node (ref "U4") (pin "16") (pinfunction "AOUT1_16") (pintype "output"))
    )
    (net (code "59") (name "Net-(U4-AOUT2)") (class "Default")
      (node (ref "M1") (pin "4") (pinfunction "4_4") (pintype "passive"))
      (node (ref "M6") (pin "4") (pinfunction "4_4") (pintype "passive"))
      (node (ref "U4") (pin "2") (pinfunction "AOUT2_2") (pintype "output"))
    )
    (net (code "60") (name "Net-(U4-BOUT1)") (class "Default")
      (node (ref "M2") (pin "3") (pinfunction "3_3") (pintype "passive"))
      (node (ref "U4") (pin "5") (pinfunction "BOUT1_5") (pintype "bidirectional"))
    )
    (net (code "61") (name "Net-(U4-BOUT2)") (class "Default")
      (node (ref "M2") (pin "4") (pinfunction "4_4") (pintype "passive"))
      (node (ref "U4") (pin "3") (pinfunction "BOUT2_3") (pintype "output"))
    )
    (net (code "62") (name "Net-(U4-NSLEEP)") (class "Default")
      (node (ref "R30") (pin "2") (pinfunction "2_2") (pintype "passive"))
      (node (ref "U4") (pin "15") (pinfunction "NSLEEP_15") (pintype "input"))
    )
    (net (code "63") (name "Net-(U4-VCP)") (class "Default")
      (node (ref "C33") (pin "2") (pinfunction "2_2") (pintype "passive"))
      (node (ref "U4") (pin "9") (pinfunction "VCP_9") (pintype "bidirectional"))
    )
    (net (code "64") (name "Net-(U4-VINT)") (class "Default")
      (node (ref "C34") (pin "1") (pinfunction "1_1") (pintype "passive"))
      (node (ref "U4") (pin "12") (pinfunction "VINT_12") (pintype "power_in"))
    )
    (net (code "65") (name "SCL") (class "Default")
      (node (ref "IC1") (pin "43") (pinfunction "(SCL/INT0)PD0_43") (pintype "bidirectional"))
    )
    (net (code "66") (name "SDA") (class "Default")
      (node (ref "IC1") (pin "44") (pinfunction "(SDA/INT1)PD1_44") (pintype "bidirectional"))
    )
    (net (code "67") (name "TEMP") (class "Default")
      (node (ref "IC1") (pin "89") (pinfunction "PK0(ADC8/PCINT16)_89") (pintype "bidirectional"))
    )
    (net (code "68") (name "VBUS") (class "Default")
      (node (ref "USB") (pin "VBUS") (pinfunction "VBUS_VBUS") (pintype "power_in"))
    )
    (net (code "69") (name "VCC") (class "Default")
      (node (ref "5V_REG") (pin "+VOUT") (pinfunction "+VOUT_+VOUT") (pintype "bidirectional"))
      (node (ref "C10") (pin "1") (pinfunction "1_1") (pintype "passive"))
      (node (ref "C11") (pin "1") (pinfunction "1_1") (pintype "passive"))
      (node (ref "C12") (pin "1") (pinfunction "1_1") (pintype "passive"))
      (node (ref "C15") (pin "1") (pinfunction "1_1") (pintype "passive"))
      (node (ref "C16") (pin "1") (pinfunction "1_1") (pintype "passive"))
      (node (ref "C17") (pin "1") (pinfunction "1_1") (pintype "passive"))
      (node (ref "C19") (pin "1") (pinfunction "1_1") (pintype "passive"))
      (node (ref "C27") (pin "+") (pinfunction "+_+") (pintype "passive"))
      (node (ref "C3") (pin "1") (pinfunction "1_1") (pintype "passive"))
      (node (ref "C4") (pin "1") (pinfunction "1_1") (pintype "passive"))
      (node (ref "C6") (pin "1") (pinfunction "1_1") (pintype "passive"))
      (node (ref "C9") (pin "1") (pinfunction "1_1") (pintype "passive"))
      (node (ref "DNF") (pin "2") (pinfunction "VCC_2") (pintype "power_in"))
      (node (ref "FTDI-FT231-XQ-R") (pin "RESET#") (pinfunction "RESET#_RESET#") (pintype "bidirectional"))
      (node (ref "FTDI-FT231-XQ-R") (pin "VCC") (pinfunction "VCC_VCC") (pintype "bidirectional"))
      (node (ref "FTDI-FT231-XQ-R") (pin "VCCIO") (pinfunction "VCCIO_VCCIO") (pintype "bidirectional"))
      (node (ref "IC1") (pin "10") (pinfunction "VCC_10") (pintype "power_in"))
      (node (ref "IC1") (pin "100") (pinfunction "AVCC_100") (pintype "power_in"))
      (node (ref "IC1") (pin "31") (pinfunction "VCC1_31") (pintype "power_in"))
      (node (ref "IC1") (pin "61") (pinfunction "VCC2_61") (pintype "power_in"))
      (node (ref "IC1") (pin "80") (pinfunction "VCC3_80") (pintype "power_in"))
      (node (ref "J1") (pin "1") (pinfunction "1_1") (pintype "bidirectional"))
      (node (ref "M1") (pin "2") (pinfunction "2_2") (pintype "passive"))
      (node (ref "M2") (pin "2") (pinfunction "2_2") (pintype "passive"))
      (node (ref "M3") (pin "2") (pinfunction "2_2") (pintype "passive"))
      (node (ref "M4") (pin "2") (pinfunction "2_2") (pintype "passive"))
      (node (ref "M5") (pin "2") (pinfunction "2_2") (pintype "passive"))
      (node (ref "M6") (pin "2") (pinfunction "2_2") (pintype "passive"))
      (node (ref "R1") (pin "2") (pinfunction "2_2") (pintype "passive"))
      (node (ref "R10") (pin "1") (pinfunction "1_1") (pintype "passive"))
      (node (ref "R30") (pin "1") (pinfunction "1_1") (pintype "passive"))
      (node (ref "R45") (pin "1") (pinfunction "1_1") (pintype "passive"))
      (node (ref "R46") (pin "1") (pinfunction "1_1") (pintype "passive"))
      (node (ref "R9") (pin "1") (pinfunction "1_1") (pintype "passive"))
    )
    (net (code "70") (name "unconnected-(CN2-Pad3)") (class "Default")
      (node (ref "CN2") (pin "3") (pinfunction "3_3") (pintype "passive"))
    )
    (net (code "71") (name "unconnected-(CN2-Pad4)") (class "Default")
      (node (ref "CN2") (pin "4") (pinfunction "4_4") (pintype "passive"))
    )
    (net (code "72") (name "unconnected-(FTDI-FT231-XQ-R-PadCBUS2)") (class "Default")
      (node (ref "FTDI-FT231-XQ-R") (pin "CBUS2") (pinfunction "CBUS2_CBUS2") (pintype "bidirectional"))
    )
    (net (code "73") (name "unconnected-(FTDI-FT231-XQ-R-PadCBUS3)") (class "Default")
      (node (ref "FTDI-FT231-XQ-R") (pin "CBUS3") (pinfunction "CBUS3_CBUS3") (pintype "bidirectional"))
    )
    (net (code "74") (name "unconnected-(FTDI-FT231-XQ-R-PadCTS#)") (class "Default")
      (node (ref "FTDI-FT231-XQ-R") (pin "CTS#") (pinfunction "CTS#_CTS#") (pintype "bidirectional"))
    )
    (net (code "75") (name "unconnected-(FTDI-FT231-XQ-R-PadDCD#)") (class "Default")
      (node (ref "FTDI-FT231-XQ-R") (pin "DCD#") (pinfunction "DCD#_DCD#") (pintype "bidirectional"))
    )
    (net (code "76") (name "unconnected-(FTDI-FT231-XQ-R-PadDSR#)") (class "Default")
      (node (ref "FTDI-FT231-XQ-R") (pin "DSR#") (pinfunction "DSR#_DSR#") (pintype "bidirectional"))
    )
    (net (code "77") (name "unconnected-(FTDI-FT231-XQ-R-PadRI#)") (class "Default")
      (node (ref "FTDI-FT231-XQ-R") (pin "RI#") (pinfunction "RI#_RI#") (pintype "bidirectional"))
    )
    (net (code "78") (name "unconnected-(FTDI-FT231-XQ-R-PadRTS#)") (class "Default")
      (node (ref "FTDI-FT231-XQ-R") (pin "RTS#") (pinfunction "RTS#_RTS#") (pintype "bidirectional"))
    )
    (net (code "79") (name "unconnected-(IC1-(A8)PC0-Pad53)") (class "Default")
      (node (ref "IC1") (pin "53") (pinfunction "(A8)PC0_53") (pintype "bidirectional"))
    )
    (net (code "80") (name "unconnected-(IC1-(A9)PC1-Pad54)") (class "Default")
      (node (ref "IC1") (pin "54") (pinfunction "(A9)PC1_54") (pintype "bidirectional"))
    )
    (net (code "81") (name "unconnected-(IC1-(A10)PC2-Pad55)") (class "Default")
      (node (ref "IC1") (pin "55") (pinfunction "(A10)PC2_55") (pintype "bidirectional"))
    )
    (net (code "82") (name "unconnected-(IC1-(A11)PC3-Pad56)") (class "Default")
      (node (ref "IC1") (pin "56") (pinfunction "(A11)PC3_56") (pintype "bidirectional"))
    )
    (net (code "83") (name "unconnected-(IC1-(A12)PC4-Pad57)") (class "Default")
      (node (ref "IC1") (pin "57") (pinfunction "(A12)PC4_57") (pintype "bidirectional"))
    )
    (net (code "84") (name "unconnected-(IC1-(A13)PC5-Pad58)") (class "Default")
      (node (ref "IC1") (pin "58") (pinfunction "(A13)PC5_58") (pintype "bidirectional"))
    )
    (net (code "85") (name "unconnected-(IC1-(A14)PC6-Pad59)") (class "Default")
      (node (ref "IC1") (pin "59") (pinfunction "(A14)PC6_59") (pintype "bidirectional"))
    )
    (net (code "86") (name "unconnected-(IC1-(A15)PC7-Pad60)") (class "Default")
      (node (ref "IC1") (pin "60") (pinfunction "(A15)PC7_60") (pintype "bidirectional"))
    )
    (net (code "87") (name "unconnected-(IC1-(AD1)PA1-Pad77)") (class "Default")
      (node (ref "IC1") (pin "77") (pinfunction "(AD1)PA1_77") (pintype "bidirectional"))
    )
    (net (code "88") (name "unconnected-(IC1-(AD2)PA2-Pad76)") (class "Default")
      (node (ref "IC1") (pin "76") (pinfunction "(AD2)PA2_76") (pintype "bidirectional"))
    )
    (net (code "89") (name "unconnected-(IC1-(AD6)PA6-Pad72)") (class "Default")
      (node (ref "IC1") (pin "72") (pinfunction "(AD6)PA6_72") (pintype "bidirectional"))
    )
    (net (code "90") (name "unconnected-(IC1-(AD7)PA7-Pad71)") (class "Default")
      (node (ref "IC1") (pin "71") (pinfunction "(AD7)PA7_71") (pintype "bidirectional"))
    )
    (net (code "91") (name "unconnected-(IC1-(ALE)PG2-Pad70)") (class "Default")
      (node (ref "IC1") (pin "70") (pinfunction "(ALE)PG2_70") (pintype "bidirectional"))
    )
    (net (code "92") (name "unconnected-(IC1-(CLKO{slash}ICP3{slash}INT7)PE7-Pad9)") (class "Default")
      (node (ref "IC1") (pin "9") (pinfunction "(CLKO/ICP3/INT7)PE7_9") (pintype "bidirectional"))
    )
    (net (code "93") (name "unconnected-(IC1-(ICP1)PD4-Pad47)") (class "Default")
      (node (ref "IC1") (pin "47") (pinfunction "(ICP1)PD4_47") (pintype "bidirectional"))
    )
    (net (code "94") (name "unconnected-(IC1-(OC0B)PG5-Pad1)") (class "Default")
      (node (ref "IC1") (pin "1") (pinfunction "(OC0B)PG5_1") (pintype "bidirectional"))
    )
    (net (code "95") (name "unconnected-(IC1-(RD)PG1-Pad52)") (class "Default")
      (node (ref "IC1") (pin "52") (pinfunction "(RD)PG1_52") (pintype "bidirectional"))
    )
    (net (code "96") (name "unconnected-(IC1-(RXD1{slash}INT2)PD2-Pad45)") (class "Default")
      (node (ref "IC1") (pin "45") (pinfunction "(RXD1/INT2)PD2_45") (pintype "bidirectional"))
    )
    (net (code "97") (name "unconnected-(IC1-(SS{slash}PCINT0)PB0-Pad19)") (class "Default")
      (node (ref "IC1") (pin "19") (pinfunction "(SS/PCINT0)PB0_19") (pintype "bidirectional"))
    )
    (net (code "98") (name "unconnected-(IC1-(T0)PD7-Pad50)") (class "Default")
      (node (ref "IC1") (pin "50") (pinfunction "(T0)PD7_50") (pintype "bidirectional"))
    )
    (net (code "99") (name "unconnected-(IC1-(T1)PD6-Pad49)") (class "Default")
      (node (ref "IC1") (pin "49") (pinfunction "(T1)PD6_49") (pintype "bidirectional"))
    )
    (net (code "100") (name "unconnected-(IC1-(T3{slash}INT6)PE6-Pad8)") (class "Default")
      (node (ref "IC1") (pin "8") (pinfunction "(T3/INT6)PE6_8") (pintype "bidirectional"))
    )
    (net (code "101") (name "unconnected-(IC1-(TOSC1)PG4-Pad29)") (class "Default")
      (node (ref "IC1") (pin "29") (pinfunction "(TOSC1)PG4_29") (pintype "bidirectional"))
    )
    (net (code "102") (name "unconnected-(IC1-(TOSC2)PG3-Pad28)") (class "Default")
      (node (ref "IC1") (pin "28") (pinfunction "(TOSC2)PG3_28") (pintype "bidirectional"))
    )
    (net (code "103") (name "unconnected-(IC1-(TXD1{slash}INT3)PD3-Pad46)") (class "Default")
      (node (ref "IC1") (pin "46") (pinfunction "(TXD1/INT3)PD3_46") (pintype "bidirectional"))
    )
    (net (code "104") (name "unconnected-(IC1-(WR)PG0-Pad51)") (class "Default")
      (node (ref "IC1") (pin "51") (pinfunction "(WR)PG0_51") (pintype "bidirectional"))
    )
    (net (code "105") (name "unconnected-(IC1-(XCK0{slash}AIN0)PE2-Pad4)") (class "Default")
      (node (ref "IC1") (pin "4") (pinfunction "(XCK0/AIN0)PE2_4") (pintype "bidirectional"))
    )
    (net (code "106") (name "unconnected-(IC1-(XCK1)PD5-Pad48)") (class "Default")
      (node (ref "IC1") (pin "48") (pinfunction "(XCK1)PD5_48") (pintype "bidirectional"))
    )
    (net (code "107") (name "unconnected-(IC1-AREF-Pad98)") (class "Default")
      (node (ref "IC1") (pin "98") (pinfunction "AREF_98") (pintype "bidirectional"))
    )
    (net (code "108") (name "unconnected-(IC1-PH0(RXD2)-Pad12)") (class "Default")
      (node (ref "IC1") (pin "12") (pinfunction "PH0(RXD2)_12") (pintype "bidirectional"))
    )
    (net (code "109") (name "unconnected-(IC1-PH1(TXD2)-Pad13)") (class "Default")
      (node (ref "IC1") (pin "13") (pinfunction "PH1(TXD2)_13") (pintype "bidirectional"))
    )
    (net (code "110") (name "unconnected-(IC1-PH2(XCK2)-Pad14)") (class "Default")
      (node (ref "IC1") (pin "14") (pinfunction "PH2(XCK2)_14") (pintype "bidirectional"))
    )
    (net (code "111") (name "unconnected-(IC1-PH7(T4)-Pad27)") (class "Default")
      (node (ref "IC1") (pin "27") (pinfunction "PH7(T4)_27") (pintype "bidirectional"))
    )
    (net (code "112") (name "unconnected-(IC1-PJ0(RXD3{slash}PCINT9)-Pad63)") (class "Default")
      (node (ref "IC1") (pin "63") (pinfunction "PJ0(RXD3/PCINT9)_63") (pintype "bidirectional"))
    )
    (net (code "113") (name "unconnected-(IC1-PJ1(TXD3{slash}PCINT10)-Pad64)") (class "Default")
      (node (ref "IC1") (pin "64") (pinfunction "PJ1(TXD3/PCINT10)_64") (pintype "bidirectional"))
    )
    (net (code "114") (name "unconnected-(IC1-PJ2(XCK3{slash}PCINT11)-Pad65)") (class "Default")
      (node (ref "IC1") (pin "65") (pinfunction "PJ2(XCK3/PCINT11)_65") (pintype "bidirectional"))
    )
    (net (code "115") (name "unconnected-(IC1-PJ3(PCINT12)-Pad66)") (class "Default")
      (node (ref "IC1") (pin "66") (pinfunction "PJ3(PCINT12)_66") (pintype "bidirectional"))
    )
    (net (code "116") (name "unconnected-(IC1-PJ4(PCINT13)-Pad67)") (class "Default")
      (node (ref "IC1") (pin "67") (pinfunction "PJ4(PCINT13)_67") (pintype "bidirectional"))
    )
    (net (code "117") (name "unconnected-(IC1-PJ5(PCINT14)-Pad68)") (class "Default")
      (node (ref "IC1") (pin "68") (pinfunction "PJ5(PCINT14)_68") (pintype "bidirectional"))
    )
    (net (code "118") (name "unconnected-(IC1-PJ6(PCINT15)-Pad69)") (class "Default")
      (node (ref "IC1") (pin "69") (pinfunction "PJ6(PCINT15)_69") (pintype "bidirectional"))
    )
    (net (code "119") (name "unconnected-(IC1-PJ7-Pad79)") (class "Default")
      (node (ref "IC1") (pin "79") (pinfunction "PJ7_79") (pintype "bidirectional"))
    )
    (net (code "120") (name "unconnected-(IC1-PK1(ADC9{slash}PCINT17)-Pad88)") (class "Default")
      (node (ref "IC1") (pin "88") (pinfunction "PK1(ADC9/PCINT17)_88") (pintype "bidirectional"))
    )
    (net (code "121") (name "unconnected-(IC1-PK2(ADC10{slash}PCINT18)-Pad87)") (class "Default")
      (node (ref "IC1") (pin "87") (pinfunction "PK2(ADC10/PCINT18)_87") (pintype "bidirectional"))
    )
    (net (code "122") (name "unconnected-(IC1-PK3(ADC11{slash}PCINT19)-Pad86)") (class "Default")
      (node (ref "IC1") (pin "86") (pinfunction "PK3(ADC11/PCINT19)_86") (pintype "bidirectional"))
    )
    (net (code "123") (name "unconnected-(IC1-PK4(ADC12{slash}PCINT20)-Pad85)") (class "Default")
      (node (ref "IC1") (pin "85") (pinfunction "PK4(ADC12/PCINT20)_85") (pintype "bidirectional"))
    )
    (net (code "124") (name "unconnected-(IC1-PK5(ADC13{slash}PCINT21)-Pad84)") (class "Default")
      (node (ref "IC1") (pin "84") (pinfunction "PK5(ADC13/PCINT21)_84") (pintype "bidirectional"))
    )
    (net (code "125") (name "unconnected-(IC1-PK6(ADC14{slash}PCINT22)-Pad83)") (class "Default")
      (node (ref "IC1") (pin "83") (pinfunction "PK6(ADC14/PCINT22)_83") (pintype "bidirectional"))
    )
    (net (code "126") (name "unconnected-(IC1-PK7(ADC15{slash}PCINT23)-Pad82)") (class "Default")
      (node (ref "IC1") (pin "82") (pinfunction "PK7(ADC15/PCINT23)_82") (pintype "bidirectional"))
    )
    (net (code "127") (name "unconnected-(IC1-PL0(ICP4)-Pad35)") (class "Default")
      (node (ref "IC1") (pin "35") (pinfunction "PL0(ICP4)_35") (pintype "bidirectional"))
    )
    (net (code "128") (name "unconnected-(IC1-PL1(ICP5)-Pad36)") (class "Default")
      (node (ref "IC1") (pin "36") (pinfunction "PL1(ICP5)_36") (pintype "bidirectional"))
    )
    (net (code "129") (name "unconnected-(IC1-PL3(OC5A)-Pad38)") (class "Default")
      (node (ref "IC1") (pin "38") (pinfunction "PL3(OC5A)_38") (pintype "bidirectional"))
    )
    (net (code "130") (name "unconnected-(IC1-PL4(OC5B)-Pad39)") (class "Default")
      (node (ref "IC1") (pin "39") (pinfunction "PL4(OC5B)_39") (pintype "bidirectional"))
    )
    (net (code "131") (name "unconnected-(IC1-PL5(OC5C)-Pad40)") (class "Default")
      (node (ref "IC1") (pin "40") (pinfunction "PL5(OC5C)_40") (pintype "bidirectional"))
    )
    (net (code "132") (name "unconnected-(IC1-PL6-Pad41)") (class "Default")
      (node (ref "IC1") (pin "41") (pinfunction "PL6_41") (pintype "bidirectional"))
    )
    (net (code "133") (name "unconnected-(IC1-PL7-Pad42)") (class "Default")
      (node (ref "IC1") (pin "42") (pinfunction "PL7_42") (pintype "bidirectional"))
    )
    (net (code "134") (name "unconnected-(U2-NFAULT-Pad6)") (class "Default")
      (node (ref "U2") (pin "6") (pinfunction "NFAULT_6") (pintype "output"))
    )
    (net (code "135") (name "unconnected-(U3-BIN1-Pad7)") (class "Default")
      (node (ref "U3") (pin "7") (pinfunction "BIN1_7") (pintype "input"))
    )
    (net (code "136") (name "unconnected-(U3-BIN2-Pad8)") (class "Default")
      (node (ref "U3") (pin "8") (pinfunction "BIN2_8") (pintype "input"))
    )
    (net (code "137") (name "unconnected-(U3-BOUT1-Pad5)") (class "Default")
      (node (ref "U3") (pin "5") (pinfunction "BOUT1_5") (pintype "bidirectional"))
    )
    (net (code "138") (name "unconnected-(U3-BOUT2-Pad3)") (class "Default")
      (node (ref "U3") (pin "3") (pinfunction "BOUT2_3") (pintype "output"))
    )
    (net (code "139") (name "unconnected-(U3-NFAULT-Pad6)") (class "Default")
      (node (ref "U3") (pin "6") (pinfunction "NFAULT_6") (pintype "output"))
    )
    (net (code "140") (name "unconnected-(U4-NFAULT-Pad6)") (class "Default")
      (node (ref "U4") (pin "6") (pinfunction "NFAULT_6") (pintype "output"))
    )
  )
)
